# R210X.net
KiCad netlist of a schematic drawn in EAGLE
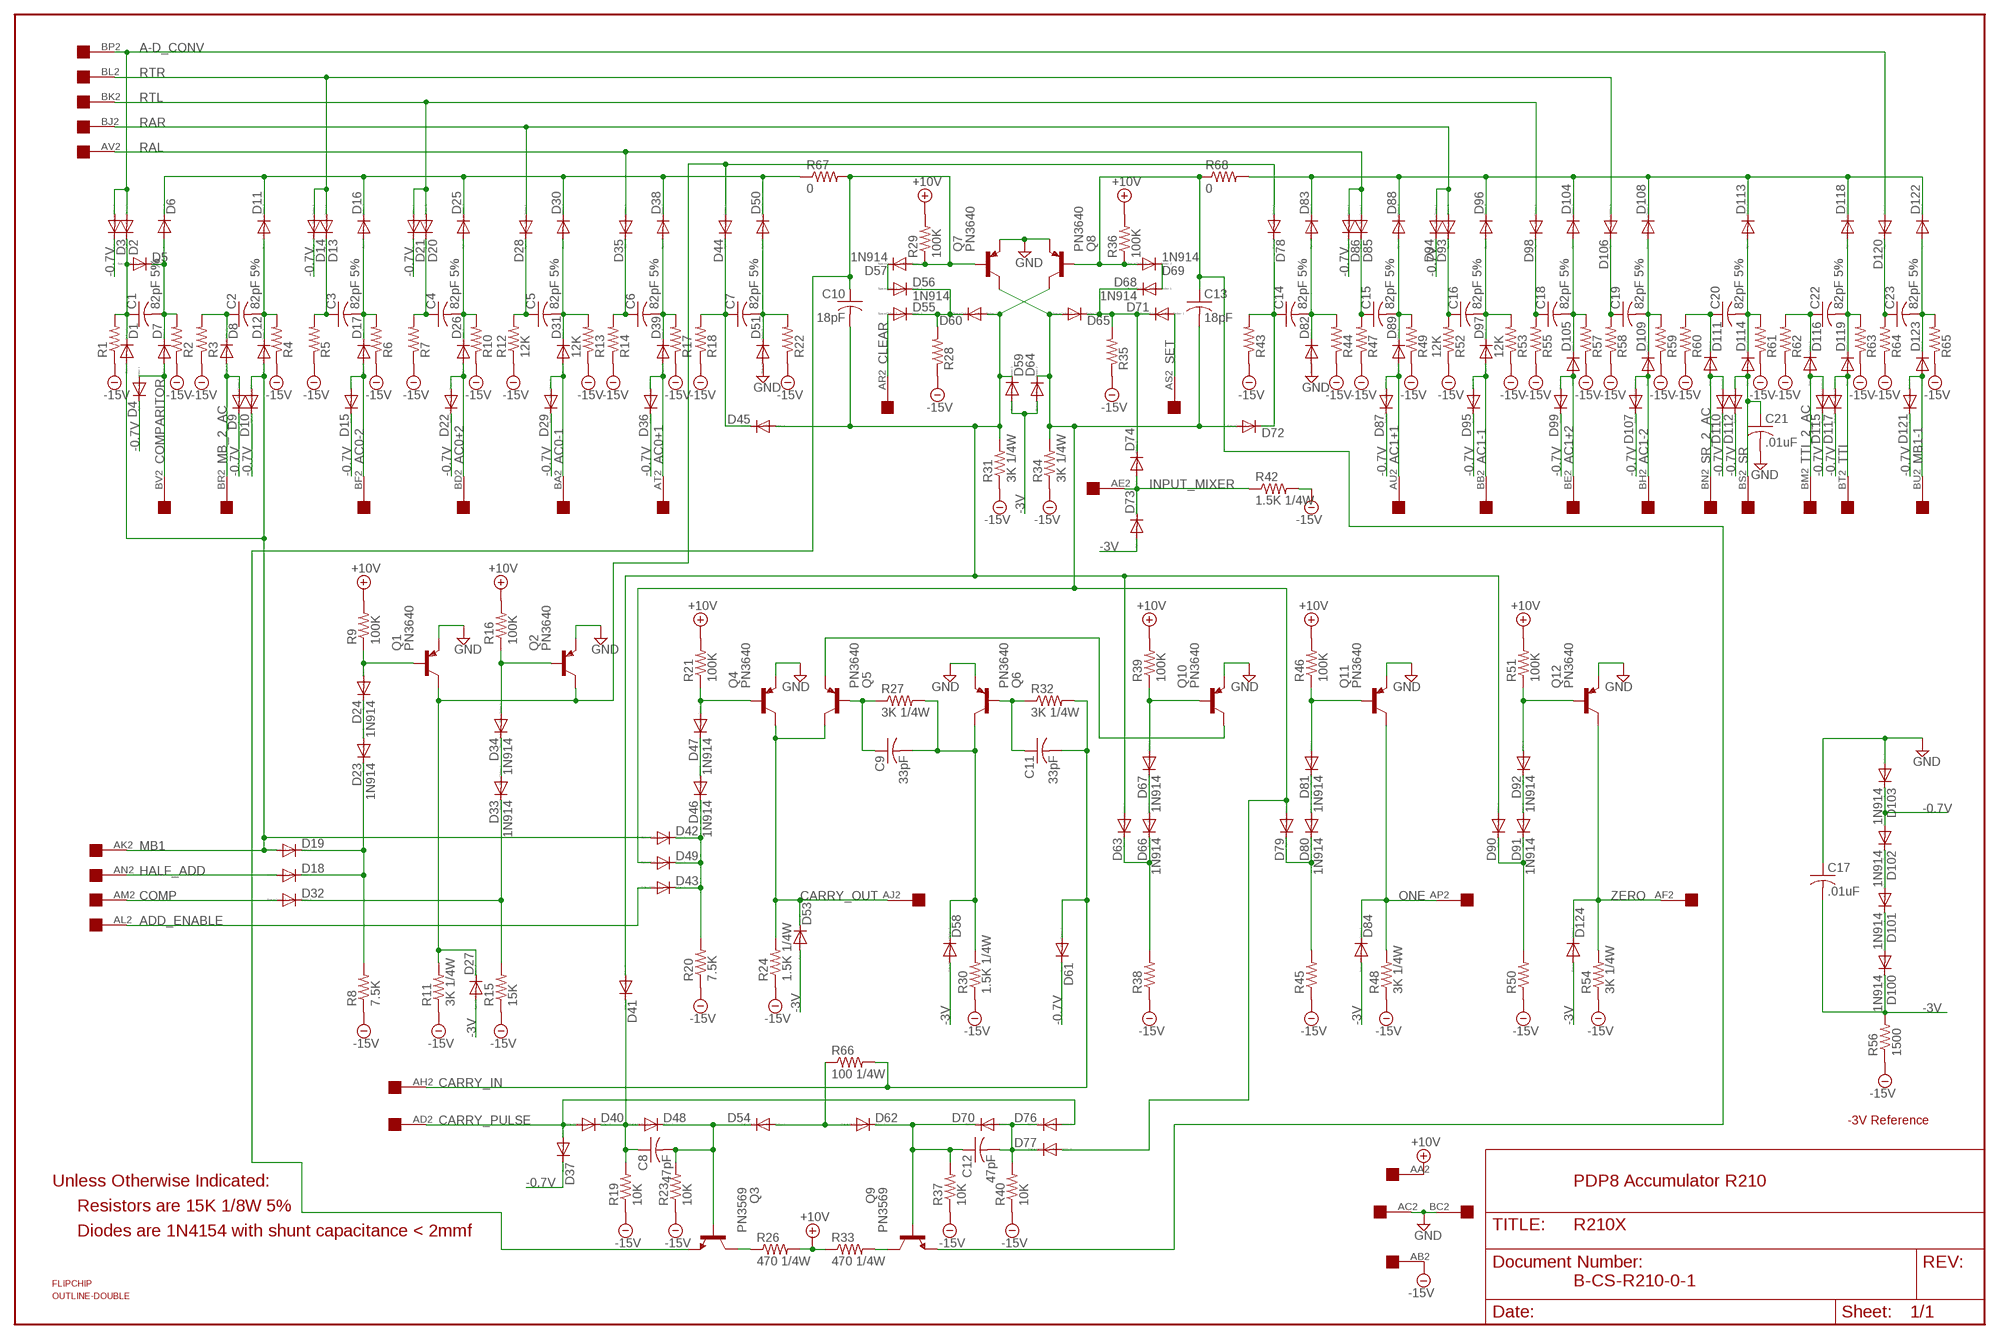
[diagram p0: schematic, sheet 1]

(export (version "E")
  (design (tool "Eeschema 10.0.6"))
  (components
    (comp (ref "C1")
      (value "82pF 5%")
      (footprint "eagle-import:C075-032X103")
      (libsource (lib "eagle-import") (part "C-US075-032X103"))
    )
    (comp (ref "C2")
      (value "82pF 5%")
      (footprint "eagle-import:C075-032X103")
      (libsource (lib "eagle-import") (part "C-US075-032X103"))
    )
    (comp (ref "C3")
      (value "82pF 5%")
      (footprint "eagle-import:C075-032X103")
      (libsource (lib "eagle-import") (part "C-US075-032X103"))
    )
    (comp (ref "C4")
      (value "82pF 5%")
      (footprint "eagle-import:C075-032X103")
      (libsource (lib "eagle-import") (part "C-US075-032X103"))
    )
    (comp (ref "C5")
      (value "82pF 5%")
      (footprint "eagle-import:C075-032X103")
      (libsource (lib "eagle-import") (part "C-US075-032X103"))
    )
    (comp (ref "C6")
      (value "82pF 5%")
      (footprint "eagle-import:C075-032X103")
      (libsource (lib "eagle-import") (part "C-US075-032X103"))
    )
    (comp (ref "C7")
      (value "82pF 5%")
      (footprint "eagle-import:C075-032X103")
      (libsource (lib "eagle-import") (part "C-US075-032X103"))
    )
    (comp (ref "C8")
      (value "47pF")
      (footprint "eagle-import:C075-032X103")
      (libsource (lib "eagle-import") (part "C-US075-032X103"))
    )
    (comp (ref "C9")
      (value "33pF")
      (footprint "eagle-import:C075-032X103")
      (libsource (lib "eagle-import") (part "C-US075-032X103"))
    )
    (comp (ref "C10")
      (value "18pF")
      (footprint "eagle-import:C075-032X103")
      (libsource (lib "eagle-import") (part "C-US075-032X103"))
    )
    (comp (ref "C11")
      (value "33pF")
      (footprint "eagle-import:C075-032X103")
      (libsource (lib "eagle-import") (part "C-US075-032X103"))
    )
    (comp (ref "C12")
      (value "47pF")
      (footprint "eagle-import:C075-032X103")
      (libsource (lib "eagle-import") (part "C-US075-032X103"))
    )
    (comp (ref "C13")
      (value "18pF")
      (footprint "eagle-import:C075-032X103")
      (libsource (lib "eagle-import") (part "C-US075-032X103"))
    )
    (comp (ref "C14")
      (value "82pF 5%")
      (footprint "eagle-import:C075-032X103")
      (libsource (lib "eagle-import") (part "C-US075-032X103"))
    )
    (comp (ref "C15")
      (value "82pF 5%")
      (footprint "eagle-import:C075-032X103")
      (libsource (lib "eagle-import") (part "C-US075-032X103"))
    )
    (comp (ref "C16")
      (value "82pF 5%")
      (footprint "eagle-import:C075-032X103")
      (libsource (lib "eagle-import") (part "C-US075-032X103"))
    )
    (comp (ref "C17")
      (value ".01uF")
      (footprint "eagle-import:C050-025X075")
      (libsource (lib "eagle-import") (part "C-US050-025X075"))
    )
    (comp (ref "C18")
      (value "82pF 5%")
      (footprint "eagle-import:C075-032X103")
      (libsource (lib "eagle-import") (part "C-US075-032X103"))
    )
    (comp (ref "C19")
      (value "82pF 5%")
      (footprint "eagle-import:C075-032X103")
      (libsource (lib "eagle-import") (part "C-US075-032X103"))
    )
    (comp (ref "C20")
      (value "82pF 5%")
      (footprint "eagle-import:C075-032X103")
      (libsource (lib "eagle-import") (part "C-US075-032X103"))
    )
    (comp (ref "C21")
      (value ".01uF")
      (footprint "eagle-import:C050-025X075")
      (libsource (lib "eagle-import") (part "C-US050-025X075"))
    )
    (comp (ref "C22")
      (value "82pF 5%")
      (footprint "eagle-import:C075-032X103")
      (libsource (lib "eagle-import") (part "C-US075-032X103"))
    )
    (comp (ref "C23")
      (value "82pF 5%")
      (footprint "eagle-import:C075-032X103")
      (libsource (lib "eagle-import") (part "C-US075-032X103"))
    )
    (comp (ref "D1")
      (value "1N4148DO35-10")
      (footprint "eagle-import:DO35-10")
      (libsource (lib "eagle-import") (part "1N4148DO35-10"))
    )
    (comp (ref "D2")
      (value "1N4148DO35-10")
      (footprint "eagle-import:DO35-10")
      (libsource (lib "eagle-import") (part "1N4148DO35-10"))
    )
    (comp (ref "D3")
      (value "1N4148DO35-10")
      (footprint "eagle-import:DO35-10")
      (libsource (lib "eagle-import") (part "1N4148DO35-10"))
    )
    (comp (ref "D4")
      (value "1N4148DO35-10")
      (footprint "eagle-import:DO35-10")
      (libsource (lib "eagle-import") (part "1N4148DO35-10"))
    )
    (comp (ref "D5")
      (value "1N4148DO35-10")
      (footprint "eagle-import:DO35-10")
      (libsource (lib "eagle-import") (part "1N4148DO35-10"))
    )
    (comp (ref "D6")
      (value "1N4148DO35-10")
      (footprint "eagle-import:DO35-10")
      (libsource (lib "eagle-import") (part "1N4148DO35-10"))
    )
    (comp (ref "D7")
      (value "1N4148DO35-10")
      (footprint "eagle-import:DO35-10")
      (libsource (lib "eagle-import") (part "1N4148DO35-10"))
    )
    (comp (ref "D8")
      (value "1N4148DO35-10")
      (footprint "eagle-import:DO35-10")
      (libsource (lib "eagle-import") (part "1N4148DO35-10"))
    )
    (comp (ref "D9")
      (value "1N4148DO35-10")
      (footprint "eagle-import:DO35-10")
      (libsource (lib "eagle-import") (part "1N4148DO35-10"))
    )
    (comp (ref "D10")
      (value "1N4148DO35-10")
      (footprint "eagle-import:DO35-10")
      (libsource (lib "eagle-import") (part "1N4148DO35-10"))
    )
    (comp (ref "D11")
      (value "1N4148DO35-10")
      (footprint "eagle-import:DO35-10")
      (libsource (lib "eagle-import") (part "1N4148DO35-10"))
    )
    (comp (ref "D12")
      (value "1N4148DO35-10")
      (footprint "eagle-import:DO35-10")
      (libsource (lib "eagle-import") (part "1N4148DO35-10"))
    )
    (comp (ref "D13")
      (value "1N4148DO35-10")
      (footprint "eagle-import:DO35-10")
      (libsource (lib "eagle-import") (part "1N4148DO35-10"))
    )
    (comp (ref "D14")
      (value "1N4148DO35-10")
      (footprint "eagle-import:DO35-10")
      (libsource (lib "eagle-import") (part "1N4148DO35-10"))
    )
    (comp (ref "D15")
      (value "1N4148DO35-10")
      (footprint "eagle-import:DO35-10")
      (libsource (lib "eagle-import") (part "1N4148DO35-10"))
    )
    (comp (ref "D16")
      (value "1N4148DO35-10")
      (footprint "eagle-import:DO35-10")
      (libsource (lib "eagle-import") (part "1N4148DO35-10"))
    )
    (comp (ref "D17")
      (value "1N4148DO35-10")
      (footprint "eagle-import:DO35-10")
      (libsource (lib "eagle-import") (part "1N4148DO35-10"))
    )
    (comp (ref "D18")
      (value "1N4148DO35-10")
      (footprint "eagle-import:DO35-10")
      (libsource (lib "eagle-import") (part "1N4148DO35-10"))
    )
    (comp (ref "D19")
      (value "1N4148DO35-10")
      (footprint "eagle-import:DO35-10")
      (libsource (lib "eagle-import") (part "1N4148DO35-10"))
    )
    (comp (ref "D20")
      (value "1N4148DO35-10")
      (footprint "eagle-import:DO35-10")
      (libsource (lib "eagle-import") (part "1N4148DO35-10"))
    )
    (comp (ref "D21")
      (value "1N4148DO35-10")
      (footprint "eagle-import:DO35-10")
      (libsource (lib "eagle-import") (part "1N4148DO35-10"))
    )
    (comp (ref "D22")
      (value "1N4148DO35-10")
      (footprint "eagle-import:DO35-10")
      (libsource (lib "eagle-import") (part "1N4148DO35-10"))
    )
    (comp (ref "D23")
      (value "1N914")
      (footprint "eagle-import:DO35-10")
      (libsource (lib "eagle-import") (part "1N4148DO35-10"))
    )
    (comp (ref "D24")
      (value "1N914")
      (footprint "eagle-import:DO35-10")
      (libsource (lib "eagle-import") (part "1N4148DO35-10"))
    )
    (comp (ref "D25")
      (value "1N4148DO35-10")
      (footprint "eagle-import:DO35-10")
      (libsource (lib "eagle-import") (part "1N4148DO35-10"))
    )
    (comp (ref "D26")
      (value "1N4148DO35-10")
      (footprint "eagle-import:DO35-10")
      (libsource (lib "eagle-import") (part "1N4148DO35-10"))
    )
    (comp (ref "D27")
      (value "1N4148DO35-10")
      (footprint "eagle-import:DO35-10")
      (libsource (lib "eagle-import") (part "1N4148DO35-10"))
    )
    (comp (ref "D28")
      (value "1N4148DO35-10")
      (footprint "eagle-import:DO35-10")
      (libsource (lib "eagle-import") (part "1N4148DO35-10"))
    )
    (comp (ref "D29")
      (value "1N4148DO35-10")
      (footprint "eagle-import:DO35-10")
      (libsource (lib "eagle-import") (part "1N4148DO35-10"))
    )
    (comp (ref "D30")
      (value "1N4148DO35-10")
      (footprint "eagle-import:DO35-10")
      (libsource (lib "eagle-import") (part "1N4148DO35-10"))
    )
    (comp (ref "D31")
      (value "1N4148DO35-10")
      (footprint "eagle-import:DO35-10")
      (libsource (lib "eagle-import") (part "1N4148DO35-10"))
    )
    (comp (ref "D32")
      (value "1N4148DO35-10")
      (footprint "eagle-import:DO35-10")
      (libsource (lib "eagle-import") (part "1N4148DO35-10"))
    )
    (comp (ref "D33")
      (value "1N914")
      (footprint "eagle-import:DO35-10")
      (libsource (lib "eagle-import") (part "1N4148DO35-10"))
    )
    (comp (ref "D34")
      (value "1N914")
      (footprint "eagle-import:DO35-10")
      (libsource (lib "eagle-import") (part "1N4148DO35-10"))
    )
    (comp (ref "D35")
      (value "1N4148DO35-10")
      (footprint "eagle-import:DO35-10")
      (libsource (lib "eagle-import") (part "1N4148DO35-10"))
    )
    (comp (ref "D36")
      (value "1N4148DO35-10")
      (footprint "eagle-import:DO35-10")
      (libsource (lib "eagle-import") (part "1N4148DO35-10"))
    )
    (comp (ref "D37")
      (value "1N4148DO35-10")
      (footprint "eagle-import:DO35-10")
      (libsource (lib "eagle-import") (part "1N4148DO35-10"))
    )
    (comp (ref "D38")
      (value "1N4148DO35-10")
      (footprint "eagle-import:DO35-10")
      (libsource (lib "eagle-import") (part "1N4148DO35-10"))
    )
    (comp (ref "D39")
      (value "1N4148DO35-10")
      (footprint "eagle-import:DO35-10")
      (libsource (lib "eagle-import") (part "1N4148DO35-10"))
    )
    (comp (ref "D40")
      (value "1N4148DO35-10")
      (footprint "eagle-import:DO35-10")
      (libsource (lib "eagle-import") (part "1N4148DO35-10"))
    )
    (comp (ref "D41")
      (value "1N4148DO35-10")
      (footprint "eagle-import:DO35-10")
      (libsource (lib "eagle-import") (part "1N4148DO35-10"))
    )
    (comp (ref "D42")
      (value "1N4148DO35-10")
      (footprint "eagle-import:DO35-10")
      (libsource (lib "eagle-import") (part "1N4148DO35-10"))
    )
    (comp (ref "D43")
      (value "1N4148DO35-10")
      (footprint "eagle-import:DO35-10")
      (libsource (lib "eagle-import") (part "1N4148DO35-10"))
    )
    (comp (ref "D44")
      (value "1N4148DO35-10")
      (footprint "eagle-import:DO35-10")
      (libsource (lib "eagle-import") (part "1N4148DO35-10"))
    )
    (comp (ref "D45")
      (value "1N4148DO35-10")
      (footprint "eagle-import:DO35-10")
      (libsource (lib "eagle-import") (part "1N4148DO35-10"))
    )
    (comp (ref "D46")
      (value "1N914")
      (footprint "eagle-import:DO35-10")
      (libsource (lib "eagle-import") (part "1N4148DO35-10"))
    )
    (comp (ref "D47")
      (value "1N914")
      (footprint "eagle-import:DO35-10")
      (libsource (lib "eagle-import") (part "1N4148DO35-10"))
    )
    (comp (ref "D48")
      (value "1N4148DO35-10")
      (footprint "eagle-import:DO35-10")
      (libsource (lib "eagle-import") (part "1N4148DO35-10"))
    )
    (comp (ref "D49")
      (value "1N4148DO35-10")
      (footprint "eagle-import:DO35-10")
      (libsource (lib "eagle-import") (part "1N4148DO35-10"))
    )
    (comp (ref "D50")
      (value "1N4148DO35-10")
      (footprint "eagle-import:DO35-10")
      (libsource (lib "eagle-import") (part "1N4148DO35-10"))
    )
    (comp (ref "D51")
      (value "1N4148DO35-10")
      (footprint "eagle-import:DO35-10")
      (libsource (lib "eagle-import") (part "1N4148DO35-10"))
    )
    (comp (ref "D53")
      (value "1N4148DO35-10")
      (footprint "eagle-import:DO35-10")
      (libsource (lib "eagle-import") (part "1N4148DO35-10"))
    )
    (comp (ref "D54")
      (value "1N4148DO35-10")
      (footprint "eagle-import:DO35-10")
      (libsource (lib "eagle-import") (part "1N4148DO35-10"))
    )
    (comp (ref "D55")
      (value "1N4148DO35-10")
      (footprint "eagle-import:DO35-10")
      (libsource (lib "eagle-import") (part "1N4148DO35-10"))
    )
    (comp (ref "D56")
      (value "1N914")
      (footprint "eagle-import:DO35-10")
      (libsource (lib "eagle-import") (part "1N4148DO35-10"))
    )
    (comp (ref "D57")
      (value "1N914")
      (footprint "eagle-import:DO35-10")
      (libsource (lib "eagle-import") (part "1N4148DO35-10"))
    )
    (comp (ref "D58")
      (value "1N4148DO35-10")
      (footprint "eagle-import:DO35-10")
      (libsource (lib "eagle-import") (part "1N4148DO35-10"))
    )
    (comp (ref "D59")
      (value "1N4148DO35-10")
      (footprint "eagle-import:DO35-10")
      (libsource (lib "eagle-import") (part "1N4148DO35-10"))
    )
    (comp (ref "D60")
      (value "1N4148DO35-10")
      (footprint "eagle-import:DO35-10")
      (libsource (lib "eagle-import") (part "1N4148DO35-10"))
    )
    (comp (ref "D61")
      (value "1N4148DO35-10")
      (footprint "eagle-import:DO35-10")
      (libsource (lib "eagle-import") (part "1N4148DO35-10"))
    )
    (comp (ref "D62")
      (value "1N4148DO35-10")
      (footprint "eagle-import:DO35-10")
      (libsource (lib "eagle-import") (part "1N4148DO35-10"))
    )
    (comp (ref "D63")
      (value "1N4148DO35-10")
      (footprint "eagle-import:DO35-10")
      (libsource (lib "eagle-import") (part "1N4148DO35-10"))
    )
    (comp (ref "D64")
      (value "1N4148DO35-10")
      (footprint "eagle-import:DO35-10")
      (libsource (lib "eagle-import") (part "1N4148DO35-10"))
    )
    (comp (ref "D65")
      (value "1N4148DO35-10")
      (footprint "eagle-import:DO35-10")
      (libsource (lib "eagle-import") (part "1N4148DO35-10"))
    )
    (comp (ref "D66")
      (value "1N914")
      (footprint "eagle-import:DO35-10")
      (libsource (lib "eagle-import") (part "1N4148DO35-10"))
    )
    (comp (ref "D67")
      (value "1N914")
      (footprint "eagle-import:DO35-10")
      (libsource (lib "eagle-import") (part "1N4148DO35-10"))
    )
    (comp (ref "D68")
      (value "1N914")
      (footprint "eagle-import:DO35-10")
      (libsource (lib "eagle-import") (part "1N4148DO35-10"))
    )
    (comp (ref "D69")
      (value "1N914")
      (footprint "eagle-import:DO35-10")
      (libsource (lib "eagle-import") (part "1N4148DO35-10"))
    )
    (comp (ref "D70")
      (value "1N4148DO35-10")
      (footprint "eagle-import:DO35-10")
      (libsource (lib "eagle-import") (part "1N4148DO35-10"))
    )
    (comp (ref "D71")
      (value "1N4148DO35-10")
      (footprint "eagle-import:DO35-10")
      (libsource (lib "eagle-import") (part "1N4148DO35-10"))
    )
    (comp (ref "D72")
      (value "1N4148DO35-10")
      (footprint "eagle-import:DO35-10")
      (libsource (lib "eagle-import") (part "1N4148DO35-10"))
    )
    (comp (ref "D73")
      (value "1N4148DO35-10")
      (footprint "eagle-import:DO35-10")
      (libsource (lib "eagle-import") (part "1N4148DO35-10"))
    )
    (comp (ref "D74")
      (value "1N4148DO35-10")
      (footprint "eagle-import:DO35-10")
      (libsource (lib "eagle-import") (part "1N4148DO35-10"))
    )
    (comp (ref "D76")
      (value "1N4148DO35-10")
      (footprint "eagle-import:DO35-10")
      (libsource (lib "eagle-import") (part "1N4148DO35-10"))
    )
    (comp (ref "D77")
      (value "1N4148DO35-10")
      (footprint "eagle-import:DO35-10")
      (libsource (lib "eagle-import") (part "1N4148DO35-10"))
    )
    (comp (ref "D78")
      (value "1N4148DO35-10")
      (footprint "eagle-import:DO35-10")
      (libsource (lib "eagle-import") (part "1N4148DO35-10"))
    )
    (comp (ref "D79")
      (value "1N4148DO35-10")
      (footprint "eagle-import:DO35-10")
      (libsource (lib "eagle-import") (part "1N4148DO35-10"))
    )
    (comp (ref "D80")
      (value "1N914")
      (footprint "eagle-import:DO35-10")
      (libsource (lib "eagle-import") (part "1N4148DO35-10"))
    )
    (comp (ref "D81")
      (value "1N914")
      (footprint "eagle-import:DO35-10")
      (libsource (lib "eagle-import") (part "1N4148DO35-10"))
    )
    (comp (ref "D82")
      (value "1N4148DO35-10")
      (footprint "eagle-import:DO35-10")
      (libsource (lib "eagle-import") (part "1N4148DO35-10"))
    )
    (comp (ref "D83")
      (value "1N4148DO35-10")
      (footprint "eagle-import:DO35-10")
      (libsource (lib "eagle-import") (part "1N4148DO35-10"))
    )
    (comp (ref "D84")
      (value "1N4148DO35-10")
      (footprint "eagle-import:DO35-10")
      (libsource (lib "eagle-import") (part "1N4148DO35-10"))
    )
    (comp (ref "D85")
      (value "1N4148DO35-10")
      (footprint "eagle-import:DO35-10")
      (libsource (lib "eagle-import") (part "1N4148DO35-10"))
    )
    (comp (ref "D86")
      (value "1N4148DO35-10")
      (footprint "eagle-import:DO35-10")
      (libsource (lib "eagle-import") (part "1N4148DO35-10"))
    )
    (comp (ref "D87")
      (value "1N4148DO35-10")
      (footprint "eagle-import:DO35-10")
      (libsource (lib "eagle-import") (part "1N4148DO35-10"))
    )
    (comp (ref "D88")
      (value "1N4148DO35-10")
      (footprint "eagle-import:DO35-10")
      (libsource (lib "eagle-import") (part "1N4148DO35-10"))
    )
    (comp (ref "D89")
      (value "1N4148DO35-10")
      (footprint "eagle-import:DO35-10")
      (libsource (lib "eagle-import") (part "1N4148DO35-10"))
    )
    (comp (ref "D90")
      (value "1N4148DO35-10")
      (footprint "eagle-import:DO35-10")
      (libsource (lib "eagle-import") (part "1N4148DO35-10"))
    )
    (comp (ref "D91")
      (value "1N914")
      (footprint "eagle-import:DO35-10")
      (libsource (lib "eagle-import") (part "1N4148DO35-10"))
    )
    (comp (ref "D92")
      (value "1N914")
      (footprint "eagle-import:DO35-10")
      (libsource (lib "eagle-import") (part "1N4148DO35-10"))
    )
    (comp (ref "D93")
      (value "1N4148DO35-10")
      (footprint "eagle-import:DO35-10")
      (libsource (lib "eagle-import") (part "1N4148DO35-10"))
    )
    (comp (ref "D94")
      (value "1N4148DO35-10")
      (footprint "eagle-import:DO35-10")
      (libsource (lib "eagle-import") (part "1N4148DO35-10"))
    )
    (comp (ref "D95")
      (value "1N4148DO35-10")
      (footprint "eagle-import:DO35-10")
      (libsource (lib "eagle-import") (part "1N4148DO35-10"))
    )
    (comp (ref "D96")
      (value "1N4148DO35-10")
      (footprint "eagle-import:DO35-10")
      (libsource (lib "eagle-import") (part "1N4148DO35-10"))
    )
    (comp (ref "D97")
      (value "1N4148DO35-10")
      (footprint "eagle-import:DO35-10")
      (libsource (lib "eagle-import") (part "1N4148DO35-10"))
    )
    (comp (ref "D98")
      (value "1N4148DO35-10")
      (footprint "eagle-import:DO35-10")
      (libsource (lib "eagle-import") (part "1N4148DO35-10"))
    )
    (comp (ref "D99")
      (value "1N4148DO35-10")
      (footprint "eagle-import:DO35-10")
      (libsource (lib "eagle-import") (part "1N4148DO35-10"))
    )
    (comp (ref "D100")
      (value "1N914")
      (footprint "eagle-import:DO35-10")
      (libsource (lib "eagle-import") (part "1N4148DO35-10"))
    )
    (comp (ref "D101")
      (value "1N914")
      (footprint "eagle-import:DO35-10")
      (libsource (lib "eagle-import") (part "1N4148DO35-10"))
    )
    (comp (ref "D102")
      (value "1N914")
      (footprint "eagle-import:DO35-10")
      (libsource (lib "eagle-import") (part "1N4148DO35-10"))
    )
    (comp (ref "D103")
      (value "1N914")
      (footprint "eagle-import:DO35-10")
      (libsource (lib "eagle-import") (part "1N4148DO35-10"))
    )
    (comp (ref "D104")
      (value "1N4148DO35-10")
      (footprint "eagle-import:DO35-10")
      (libsource (lib "eagle-import") (part "1N4148DO35-10"))
    )
    (comp (ref "D105")
      (value "1N4148DO35-10")
      (footprint "eagle-import:DO35-10")
      (libsource (lib "eagle-import") (part "1N4148DO35-10"))
    )
    (comp (ref "D106")
      (value "1N4148DO35-10")
      (footprint "eagle-import:DO35-10")
      (libsource (lib "eagle-import") (part "1N4148DO35-10"))
    )
    (comp (ref "D107")
      (value "1N4148DO35-10")
      (footprint "eagle-import:DO35-10")
      (libsource (lib "eagle-import") (part "1N4148DO35-10"))
    )
    (comp (ref "D108")
      (value "1N4148DO35-10")
      (footprint "eagle-import:DO35-10")
      (libsource (lib "eagle-import") (part "1N4148DO35-10"))
    )
    (comp (ref "D109")
      (value "1N4148DO35-10")
      (footprint "eagle-import:DO35-10")
      (libsource (lib "eagle-import") (part "1N4148DO35-10"))
    )
    (comp (ref "D110")
      (value "1N4148DO35-10")
      (footprint "eagle-import:DO35-10")
      (libsource (lib "eagle-import") (part "1N4148DO35-10"))
    )
    (comp (ref "D111")
      (value "1N4148DO35-10")
      (footprint "eagle-import:DO35-10")
      (libsource (lib "eagle-import") (part "1N4148DO35-10"))
    )
    (comp (ref "D112")
      (value "1N4148DO35-10")
      (footprint "eagle-import:DO35-10")
      (libsource (lib "eagle-import") (part "1N4148DO35-10"))
    )
    (comp (ref "D113")
      (value "1N4148DO35-10")
      (footprint "eagle-import:DO35-10")
      (libsource (lib "eagle-import") (part "1N4148DO35-10"))
    )
    (comp (ref "D114")
      (value "1N4148DO35-10")
      (footprint "eagle-import:DO35-10")
      (libsource (lib "eagle-import") (part "1N4148DO35-10"))
    )
    (comp (ref "D115")
      (value "1N4148DO35-10")
      (footprint "eagle-import:DO35-10")
      (libsource (lib "eagle-import") (part "1N4148DO35-10"))
    )
    (comp (ref "D116")
      (value "1N4148DO35-10")
      (footprint "eagle-import:DO35-10")
      (libsource (lib "eagle-import") (part "1N4148DO35-10"))
    )
    (comp (ref "D117")
      (value "1N4148DO35-10")
      (footprint "eagle-import:DO35-10")
      (libsource (lib "eagle-import") (part "1N4148DO35-10"))
    )
    (comp (ref "D118")
      (value "1N4148DO35-10")
      (footprint "eagle-import:DO35-10")
      (libsource (lib "eagle-import") (part "1N4148DO35-10"))
    )
    (comp (ref "D119")
      (value "1N4148DO35-10")
      (footprint "eagle-import:DO35-10")
      (libsource (lib "eagle-import") (part "1N4148DO35-10"))
    )
    (comp (ref "D120")
      (value "1N4148DO35-10")
      (footprint "eagle-import:DO35-10")
      (libsource (lib "eagle-import") (part "1N4148DO35-10"))
    )
    (comp (ref "D121")
      (value "1N4148DO35-10")
      (footprint "eagle-import:DO35-10")
      (libsource (lib "eagle-import") (part "1N4148DO35-10"))
    )
    (comp (ref "D122")
      (value "1N4148DO35-10")
      (footprint "eagle-import:DO35-10")
      (libsource (lib "eagle-import") (part "1N4148DO35-10"))
    )
    (comp (ref "D123")
      (value "1N4148DO35-10")
      (footprint "eagle-import:DO35-10")
      (libsource (lib "eagle-import") (part "1N4148DO35-10"))
    )
    (comp (ref "D124")
      (value "1N4148DO35-10")
      (footprint "eagle-import:DO35-10")
      (libsource (lib "eagle-import") (part "1N4148DO35-10"))
    )
    (comp (ref "Q1")
      (value "PN3640")
      (footprint "eagle-import:TO39")
      (libsource (lib "eagle-import") (part "2N3637"))
    )
    (comp (ref "Q2")
      (value "PN3640")
      (footprint "eagle-import:TO39")
      (libsource (lib "eagle-import") (part "2N3637"))
    )
    (comp (ref "Q3")
      (value "PN3569")
      (footprint "eagle-import:TO5")
      (libsource (lib "eagle-import") (part "2N2102"))
    )
    (comp (ref "Q4")
      (value "PN3640")
      (footprint "eagle-import:TO39")
      (libsource (lib "eagle-import") (part "2N3637"))
    )
    (comp (ref "Q5")
      (value "PN3640")
      (footprint "eagle-import:TO39")
      (libsource (lib "eagle-import") (part "2N3637"))
    )
    (comp (ref "Q6")
      (value "PN3640")
      (footprint "eagle-import:TO39")
      (libsource (lib "eagle-import") (part "2N3637"))
    )
    (comp (ref "Q7")
      (value "PN3640")
      (footprint "eagle-import:TO39")
      (libsource (lib "eagle-import") (part "2N3637"))
    )
    (comp (ref "Q8")
      (value "PN3640")
      (footprint "eagle-import:TO39")
      (libsource (lib "eagle-import") (part "2N3637"))
    )
    (comp (ref "Q9")
      (value "PN3569")
      (footprint "eagle-import:TO5")
      (libsource (lib "eagle-import") (part "2N2102"))
    )
    (comp (ref "Q10")
      (value "PN3640")
      (footprint "eagle-import:TO39")
      (libsource (lib "eagle-import") (part "2N3637"))
    )
    (comp (ref "Q11")
      (value "PN3640")
      (footprint "eagle-import:TO39")
      (libsource (lib "eagle-import") (part "2N3637"))
    )
    (comp (ref "Q12")
      (value "PN3640")
      (footprint "eagle-import:TO39")
      (libsource (lib "eagle-import") (part "2N3637"))
    )
    (comp (ref "R1")
      (value "R-US_0207/10")
      (footprint "eagle-import:0207_10")
      (libsource (lib "eagle-import") (part "R-US_0207/10"))
    )
    (comp (ref "R2")
      (value "R-US_0207/10")
      (footprint "eagle-import:0207_10")
      (libsource (lib "eagle-import") (part "R-US_0207/10"))
    )
    (comp (ref "R3")
      (value "R-US_0207/10")
      (footprint "eagle-import:0207_10")
      (libsource (lib "eagle-import") (part "R-US_0207/10"))
    )
    (comp (ref "R4")
      (value "R-US_0207/10")
      (footprint "eagle-import:0207_10")
      (libsource (lib "eagle-import") (part "R-US_0207/10"))
    )
    (comp (ref "R5")
      (value "R-US_0207/10")
      (footprint "eagle-import:0207_10")
      (libsource (lib "eagle-import") (part "R-US_0207/10"))
    )
    (comp (ref "R6")
      (value "R-US_0207/10")
      (footprint "eagle-import:0207_10")
      (libsource (lib "eagle-import") (part "R-US_0207/10"))
    )
    (comp (ref "R7")
      (value "R-US_0207/10")
      (footprint "eagle-import:0207_10")
      (libsource (lib "eagle-import") (part "R-US_0207/10"))
    )
    (comp (ref "R8")
      (value "7.5K")
      (footprint "eagle-import:0207_10")
      (libsource (lib "eagle-import") (part "R-US_0207/10"))
    )
    (comp (ref "R9")
      (value "100K")
      (footprint "eagle-import:0207_10")
      (libsource (lib "eagle-import") (part "R-US_0207/10"))
    )
    (comp (ref "R10")
      (value "R-US_0207/10")
      (footprint "eagle-import:0207_10")
      (libsource (lib "eagle-import") (part "R-US_0207/10"))
    )
    (comp (ref "R11")
      (value "3K 1/4W")
      (footprint "eagle-import:0207_10")
      (libsource (lib "eagle-import") (part "R-US_0207/10"))
    )
    (comp (ref "R12")
      (value "12K")
      (footprint "eagle-import:0207_10")
      (libsource (lib "eagle-import") (part "R-US_0207/10"))
    )
    (comp (ref "R13")
      (value "12K")
      (footprint "eagle-import:0207_10")
      (libsource (lib "eagle-import") (part "R-US_0207/10"))
    )
    (comp (ref "R14")
      (value "R-US_0207/10")
      (footprint "eagle-import:0207_10")
      (libsource (lib "eagle-import") (part "R-US_0207/10"))
    )
    (comp (ref "R15")
      (value "15K")
      (footprint "eagle-import:0207_10")
      (libsource (lib "eagle-import") (part "R-US_0207/10"))
    )
    (comp (ref "R16")
      (value "100K")
      (footprint "eagle-import:0207_10")
      (libsource (lib "eagle-import") (part "R-US_0207/10"))
    )
    (comp (ref "R17")
      (value "R-US_0207/10")
      (footprint "eagle-import:0207_10")
      (libsource (lib "eagle-import") (part "R-US_0207/10"))
    )
    (comp (ref "R18")
      (value "R-US_0207/10")
      (footprint "eagle-import:0207_10")
      (libsource (lib "eagle-import") (part "R-US_0207/10"))
    )
    (comp (ref "R19")
      (value "10K")
      (footprint "eagle-import:0207_10")
      (libsource (lib "eagle-import") (part "R-US_0207/10"))
    )
    (comp (ref "R20")
      (value "7.5K")
      (footprint "eagle-import:0207_10")
      (libsource (lib "eagle-import") (part "R-US_0207/10"))
    )
    (comp (ref "R21")
      (value "100K")
      (footprint "eagle-import:0207_10")
      (libsource (lib "eagle-import") (part "R-US_0207/10"))
    )
    (comp (ref "R22")
      (value "R-US_0207/10")
      (footprint "eagle-import:0207_10")
      (libsource (lib "eagle-import") (part "R-US_0207/10"))
    )
    (comp (ref "R23")
      (value "10K")
      (footprint "eagle-import:0207_10")
      (libsource (lib "eagle-import") (part "R-US_0207/10"))
    )
    (comp (ref "R24")
      (value "1.5K 1/4W")
      (footprint "eagle-import:0207_10")
      (libsource (lib "eagle-import") (part "R-US_0207/10"))
    )
    (comp (ref "R26")
      (value "470 1/4W")
      (footprint "eagle-import:0207_10")
      (libsource (lib "eagle-import") (part "R-US_0207/10"))
    )
    (comp (ref "R27")
      (value "3K 1/4W")
      (footprint "eagle-import:0207_10")
      (libsource (lib "eagle-import") (part "R-US_0207/10"))
    )
    (comp (ref "R28")
      (value "R-US_0207/10")
      (footprint "eagle-import:0207_10")
      (libsource (lib "eagle-import") (part "R-US_0207/10"))
    )
    (comp (ref "R29")
      (value "100K")
      (footprint "eagle-import:0207_10")
      (libsource (lib "eagle-import") (part "R-US_0207/10"))
    )
    (comp (ref "R30")
      (value "1.5K 1/4W")
      (footprint "eagle-import:0207_10")
      (libsource (lib "eagle-import") (part "R-US_0207/10"))
    )
    (comp (ref "R31")
      (value "3K 1/4W")
      (footprint "eagle-import:0207_10")
      (libsource (lib "eagle-import") (part "R-US_0207/10"))
    )
    (comp (ref "R32")
      (value "3K 1/4W")
      (footprint "eagle-import:0207_10")
      (libsource (lib "eagle-import") (part "R-US_0207/10"))
    )
    (comp (ref "R33")
      (value "470 1/4W")
      (footprint "eagle-import:0207_10")
      (libsource (lib "eagle-import") (part "R-US_0207/10"))
    )
    (comp (ref "R34")
      (value "3K 1/4W")
      (footprint "eagle-import:0207_10")
      (libsource (lib "eagle-import") (part "R-US_0207/10"))
    )
    (comp (ref "R35")
      (value "R-US_0207/10")
      (footprint "eagle-import:0207_10")
      (libsource (lib "eagle-import") (part "R-US_0207/10"))
    )
    (comp (ref "R36")
      (value "100K")
      (footprint "eagle-import:0207_10")
      (libsource (lib "eagle-import") (part "R-US_0207/10"))
    )
    (comp (ref "R37")
      (value "10K")
      (footprint "eagle-import:0207_10")
      (libsource (lib "eagle-import") (part "R-US_0207/10"))
    )
    (comp (ref "R38")
      (value "R-US_0207/10")
      (footprint "eagle-import:0207_10")
      (libsource (lib "eagle-import") (part "R-US_0207/10"))
    )
    (comp (ref "R39")
      (value "100K")
      (footprint "eagle-import:0207_10")
      (libsource (lib "eagle-import") (part "R-US_0207/10"))
    )
    (comp (ref "R40")
      (value "10K")
      (footprint "eagle-import:0207_10")
      (libsource (lib "eagle-import") (part "R-US_0207/10"))
    )
    (comp (ref "R42")
      (value "1.5K 1/4W")
      (footprint "eagle-import:0207_10")
      (libsource (lib "eagle-import") (part "R-US_0207/10"))
    )
    (comp (ref "R43")
      (value "R-US_0207/10")
      (footprint "eagle-import:0207_10")
      (libsource (lib "eagle-import") (part "R-US_0207/10"))
    )
    (comp (ref "R44")
      (value "R-US_0207/10")
      (footprint "eagle-import:0207_10")
      (libsource (lib "eagle-import") (part "R-US_0207/10"))
    )
    (comp (ref "R45")
      (value "R-US_0207/10")
      (footprint "eagle-import:0207_10")
      (libsource (lib "eagle-import") (part "R-US_0207/10"))
    )
    (comp (ref "R46")
      (value "100K")
      (footprint "eagle-import:0207_10")
      (libsource (lib "eagle-import") (part "R-US_0207/10"))
    )
    (comp (ref "R47")
      (value "R-US_0207/10")
      (footprint "eagle-import:0207_10")
      (libsource (lib "eagle-import") (part "R-US_0207/10"))
    )
    (comp (ref "R48")
      (value "3K 1/4W")
      (footprint "eagle-import:0207_10")
      (libsource (lib "eagle-import") (part "R-US_0207/10"))
    )
    (comp (ref "R49")
      (value "R-US_0207/10")
      (footprint "eagle-import:0207_10")
      (libsource (lib "eagle-import") (part "R-US_0207/10"))
    )
    (comp (ref "R50")
      (value "R-US_0207/10")
      (footprint "eagle-import:0207_10")
      (libsource (lib "eagle-import") (part "R-US_0207/10"))
    )
    (comp (ref "R51")
      (value "100K")
      (footprint "eagle-import:0207_10")
      (libsource (lib "eagle-import") (part "R-US_0207/10"))
    )
    (comp (ref "R52")
      (value "12K")
      (footprint "eagle-import:0207_10")
      (libsource (lib "eagle-import") (part "R-US_0207/10"))
    )
    (comp (ref "R53")
      (value "12K")
      (footprint "eagle-import:0207_10")
      (libsource (lib "eagle-import") (part "R-US_0207/10"))
    )
    (comp (ref "R54")
      (value "3K 1/4W")
      (footprint "eagle-import:0207_10")
      (libsource (lib "eagle-import") (part "R-US_0207/10"))
    )
    (comp (ref "R55")
      (value "R-US_0207/10")
      (footprint "eagle-import:0207_10")
      (libsource (lib "eagle-import") (part "R-US_0207/10"))
    )
    (comp (ref "R56")
      (value "1500")
      (footprint "eagle-import:0207_10")
      (libsource (lib "eagle-import") (part "R-US_0207/10"))
    )
    (comp (ref "R57")
      (value "R-US_0207/10")
      (footprint "eagle-import:0207_10")
      (libsource (lib "eagle-import") (part "R-US_0207/10"))
    )
    (comp (ref "R58")
      (value "R-US_0207/10")
      (footprint "eagle-import:0207_10")
      (libsource (lib "eagle-import") (part "R-US_0207/10"))
    )
    (comp (ref "R59")
      (value "R-US_0207/10")
      (footprint "eagle-import:0207_10")
      (libsource (lib "eagle-import") (part "R-US_0207/10"))
    )
    (comp (ref "R60")
      (value "R-US_0207/10")
      (footprint "eagle-import:0207_10")
      (libsource (lib "eagle-import") (part "R-US_0207/10"))
    )
    (comp (ref "R61")
      (value "R-US_0207/10")
      (footprint "eagle-import:0207_10")
      (libsource (lib "eagle-import") (part "R-US_0207/10"))
    )
    (comp (ref "R62")
      (value "R-US_0207/10")
      (footprint "eagle-import:0207_10")
      (libsource (lib "eagle-import") (part "R-US_0207/10"))
    )
    (comp (ref "R63")
      (value "R-US_0207/10")
      (footprint "eagle-import:0207_10")
      (libsource (lib "eagle-import") (part "R-US_0207/10"))
    )
    (comp (ref "R64")
      (value "R-US_0207/10")
      (footprint "eagle-import:0207_10")
      (libsource (lib "eagle-import") (part "R-US_0207/10"))
    )
    (comp (ref "R65")
      (value "R-US_0207/10")
      (footprint "eagle-import:0207_10")
      (libsource (lib "eagle-import") (part "R-US_0207/10"))
    )
    (comp (ref "R66")
      (value "100 1/4W")
      (footprint "eagle-import:0207_10")
      (libsource (lib "eagle-import") (part "R-US_0207/10"))
    )
    (comp (ref "R67")
      (value "0")
      (footprint "eagle-import:0207_10")
      (libsource (lib "eagle-import") (part "R-US_0207/10"))
    )
    (comp (ref "R68")
      (value "0")
      (footprint "eagle-import:0207_10")
      (libsource (lib "eagle-import") (part "R-US_0207/10"))
    )
    (comp (ref "U$1")
      (value "DOUBLE")
      (footprint "eagle-import:EDGE-CON4")
      (libsource (lib "eagle-import") (part "DOUBLE"))
    )
    (comp (ref "U$2")
      (value "FLIPCHIP")
      (footprint "eagle-import:FLIPCHIP")
      (libsource (lib "eagle-import") (part "FLIPCHIP"))
    )
    (comp (ref "U$3")
      (value "OUTLINE-DOUBLE")
      (footprint "eagle-import:DOUBLE")
      (libsource (lib "eagle-import") (part "OUTLINE-DOUBLE"))
    )
  )
  (nets
    (net (code "1") (name "+10V") (class "Default")
      (node (ref "R16") (pin "2") (pinfunction "2_2") (pintype "passive"))
      (node (ref "R21") (pin "2") (pinfunction "2_2") (pintype "passive"))
      (node (ref "R26") (pin "2") (pinfunction "2_2") (pintype "passive"))
      (node (ref "R29") (pin "2") (pinfunction "2_2") (pintype "passive"))
      (node (ref "R33") (pin "1") (pinfunction "1_1") (pintype "passive"))
      (node (ref "R36") (pin "2") (pinfunction "2_2") (pintype "passive"))
      (node (ref "R39") (pin "2") (pinfunction "2_2") (pintype "passive"))
      (node (ref "R46") (pin "2") (pinfunction "2_2") (pintype "passive"))
      (node (ref "R51") (pin "2") (pinfunction "2_2") (pintype "passive"))
      (node (ref "R9") (pin "2") (pinfunction "2_2") (pintype "passive"))
      (node (ref "U$1") (pin "AA2") (pinfunction "1_AA2") (pintype "bidirectional"))
    )
    (net (code "2") (name "-15V") (class "Default")
      (node (ref "R1") (pin "1") (pinfunction "1_1") (pintype "passive"))
      (node (ref "R10") (pin "1") (pinfunction "1_1") (pintype "passive"))
      (node (ref "R11") (pin "1") (pinfunction "1_1") (pintype "passive"))
      (node (ref "R12") (pin "1") (pinfunction "1_1") (pintype "passive"))
      (node (ref "R13") (pin "1") (pinfunction "1_1") (pintype "passive"))
      (node (ref "R14") (pin "1") (pinfunction "1_1") (pintype "passive"))
      (node (ref "R15") (pin "1") (pinfunction "1_1") (pintype "passive"))
      (node (ref "R17") (pin "1") (pinfunction "1_1") (pintype "passive"))
      (node (ref "R18") (pin "1") (pinfunction "1_1") (pintype "passive"))
      (node (ref "R19") (pin "1") (pinfunction "1_1") (pintype "passive"))
      (node (ref "R2") (pin "1") (pinfunction "1_1") (pintype "passive"))
      (node (ref "R20") (pin "1") (pinfunction "1_1") (pintype "passive"))
      (node (ref "R22") (pin "1") (pinfunction "1_1") (pintype "passive"))
      (node (ref "R23") (pin "1") (pinfunction "1_1") (pintype "passive"))
      (node (ref "R24") (pin "1") (pinfunction "1_1") (pintype "passive"))
      (node (ref "R28") (pin "1") (pinfunction "1_1") (pintype "passive"))
      (node (ref "R3") (pin "1") (pinfunction "1_1") (pintype "passive"))
      (node (ref "R30") (pin "1") (pinfunction "1_1") (pintype "passive"))
      (node (ref "R31") (pin "1") (pinfunction "1_1") (pintype "passive"))
      (node (ref "R34") (pin "1") (pinfunction "1_1") (pintype "passive"))
      (node (ref "R35") (pin "1") (pinfunction "1_1") (pintype "passive"))
      (node (ref "R37") (pin "1") (pinfunction "1_1") (pintype "passive"))
      (node (ref "R38") (pin "1") (pinfunction "1_1") (pintype "passive"))
      (node (ref "R4") (pin "1") (pinfunction "1_1") (pintype "passive"))
      (node (ref "R40") (pin "1") (pinfunction "1_1") (pintype "passive"))
      (node (ref "R42") (pin "2") (pinfunction "2_2") (pintype "passive"))
      (node (ref "R43") (pin "1") (pinfunction "1_1") (pintype "passive"))
      (node (ref "R44") (pin "1") (pinfunction "1_1") (pintype "passive"))
      (node (ref "R45") (pin "1") (pinfunction "1_1") (pintype "passive"))
      (node (ref "R47") (pin "1") (pinfunction "1_1") (pintype "passive"))
      (node (ref "R48") (pin "1") (pinfunction "1_1") (pintype "passive"))
      (node (ref "R49") (pin "1") (pinfunction "1_1") (pintype "passive"))
      (node (ref "R5") (pin "1") (pinfunction "1_1") (pintype "passive"))
      (node (ref "R50") (pin "1") (pinfunction "1_1") (pintype "passive"))
      (node (ref "R52") (pin "1") (pinfunction "1_1") (pintype "passive"))
      (node (ref "R53") (pin "1") (pinfunction "1_1") (pintype "passive"))
      (node (ref "R54") (pin "1") (pinfunction "1_1") (pintype "passive"))
      (node (ref "R55") (pin "1") (pinfunction "1_1") (pintype "passive"))
      (node (ref "R56") (pin "1") (pinfunction "1_1") (pintype "passive"))
      (node (ref "R57") (pin "1") (pinfunction "1_1") (pintype "passive"))
      (node (ref "R58") (pin "1") (pinfunction "1_1") (pintype "passive"))
      (node (ref "R59") (pin "1") (pinfunction "1_1") (pintype "passive"))
      (node (ref "R6") (pin "1") (pinfunction "1_1") (pintype "passive"))
      (node (ref "R60") (pin "1") (pinfunction "1_1") (pintype "passive"))
      (node (ref "R61") (pin "1") (pinfunction "1_1") (pintype "passive"))
      (node (ref "R62") (pin "1") (pinfunction "1_1") (pintype "passive"))
      (node (ref "R63") (pin "1") (pinfunction "1_1") (pintype "passive"))
      (node (ref "R64") (pin "1") (pinfunction "1_1") (pintype "passive"))
      (node (ref "R65") (pin "1") (pinfunction "1_1") (pintype "passive"))
      (node (ref "R7") (pin "1") (pinfunction "1_1") (pintype "passive"))
      (node (ref "R8") (pin "1") (pinfunction "1_1") (pintype "passive"))
      (node (ref "U$1") (pin "AB2") (pinfunction "1_AB2") (pintype "bidirectional"))
    )
    (net (code "3") (name "/-0.7V") (class "Default")
      (node (ref "D10") (pin "C") (pinfunction "C_C") (pintype "passive"))
      (node (ref "D102") (pin "A") (pinfunction "A_A") (pintype "passive"))
      (node (ref "D103") (pin "C") (pinfunction "C_C") (pintype "passive"))
      (node (ref "D107") (pin "C") (pinfunction "C_C") (pintype "passive"))
      (node (ref "D110") (pin "C") (pinfunction "C_C") (pintype "passive"))
      (node (ref "D112") (pin "C") (pinfunction "C_C") (pintype "passive"))
      (node (ref "D115") (pin "C") (pinfunction "C_C") (pintype "passive"))
      (node (ref "D117") (pin "C") (pinfunction "C_C") (pintype "passive"))
      (node (ref "D121") (pin "C") (pinfunction "C_C") (pintype "passive"))
      (node (ref "D14") (pin "C") (pinfunction "C_C") (pintype "passive"))
      (node (ref "D15") (pin "C") (pinfunction "C_C") (pintype "passive"))
      (node (ref "D21") (pin "C") (pinfunction "C_C") (pintype "passive"))
      (node (ref "D22") (pin "C") (pinfunction "C_C") (pintype "passive"))
      (node (ref "D29") (pin "C") (pinfunction "C_C") (pintype "passive"))
      (node (ref "D3") (pin "C") (pinfunction "C_C") (pintype "passive"))
      (node (ref "D36") (pin "C") (pinfunction "C_C") (pintype "passive"))
      (node (ref "D37") (pin "C") (pinfunction "C_C") (pintype "passive"))
      (node (ref "D4") (pin "C") (pinfunction "C_C") (pintype "passive"))
      (node (ref "D61") (pin "C") (pinfunction "C_C") (pintype "passive"))
      (node (ref "D86") (pin "C") (pinfunction "C_C") (pintype "passive"))
      (node (ref "D87") (pin "C") (pinfunction "C_C") (pintype "passive"))
      (node (ref "D9") (pin "C") (pinfunction "C_C") (pintype "passive"))
      (node (ref "D94") (pin "C") (pinfunction "C_C") (pintype "passive"))
      (node (ref "D95") (pin "C") (pinfunction "C_C") (pintype "passive"))
      (node (ref "D99") (pin "C") (pinfunction "C_C") (pintype "passive"))
    )
    (net (code "4") (name "/-3V") (class "Default")
      (node (ref "C17") (pin "2") (pinfunction "2_2") (pintype "passive"))
      (node (ref "D100") (pin "C") (pinfunction "C_C") (pintype "passive"))
      (node (ref "D124") (pin "A") (pinfunction "A_A") (pintype "passive"))
      (node (ref "D27") (pin "A") (pinfunction "A_A") (pintype "passive"))
      (node (ref "D53") (pin "A") (pinfunction "A_A") (pintype "passive"))
      (node (ref "D58") (pin "A") (pinfunction "A_A") (pintype "passive"))
      (node (ref "D59") (pin "A") (pinfunction "A_A") (pintype "passive"))
      (node (ref "D64") (pin "A") (pinfunction "A_A") (pintype "passive"))
      (node (ref "D73") (pin "A") (pinfunction "A_A") (pintype "passive"))
      (node (ref "D84") (pin "A") (pinfunction "A_A") (pintype "passive"))
      (node (ref "R56") (pin "2") (pinfunction "2_2") (pintype "passive"))
    )
    (net (code "5") (name "/A-D_CONV") (class "Default")
      (node (ref "D120") (pin "A") (pinfunction "A_A") (pintype "passive"))
      (node (ref "D2") (pin "A") (pinfunction "A_A") (pintype "passive"))
      (node (ref "D3") (pin "A") (pinfunction "A_A") (pintype "passive"))
      (node (ref "U$1") (pin "BP2") (pinfunction "1_BP2") (pintype "bidirectional"))
    )
    (net (code "6") (name "/AC0+1") (class "Default")
      (node (ref "D36") (pin "A") (pinfunction "A_A") (pintype "passive"))
      (node (ref "D39") (pin "A") (pinfunction "A_A") (pintype "passive"))
      (node (ref "U$1") (pin "AT2") (pinfunction "1_AT2") (pintype "bidirectional"))
    )
    (net (code "7") (name "/AC0+2") (class "Default")
      (node (ref "D22") (pin "A") (pinfunction "A_A") (pintype "passive"))
      (node (ref "D26") (pin "A") (pinfunction "A_A") (pintype "passive"))
      (node (ref "U$1") (pin "BD2") (pinfunction "1_BD2") (pintype "bidirectional"))
    )
    (net (code "8") (name "/AC0-1") (class "Default")
      (node (ref "D29") (pin "A") (pinfunction "A_A") (pintype "passive"))
      (node (ref "D31") (pin "A") (pinfunction "A_A") (pintype "passive"))
      (node (ref "U$1") (pin "BA2") (pinfunction "1_BA2") (pintype "bidirectional"))
    )
    (net (code "9") (name "/AC0-2") (class "Default")
      (node (ref "D15") (pin "A") (pinfunction "A_A") (pintype "passive"))
      (node (ref "D17") (pin "A") (pinfunction "A_A") (pintype "passive"))
      (node (ref "U$1") (pin "BF2") (pinfunction "1_BF2") (pintype "bidirectional"))
    )
    (net (code "10") (name "/AC1+1") (class "Default")
      (node (ref "D87") (pin "A") (pinfunction "A_A") (pintype "passive"))
      (node (ref "D89") (pin "A") (pinfunction "A_A") (pintype "passive"))
      (node (ref "U$1") (pin "AU2") (pinfunction "1_AU2") (pintype "bidirectional"))
    )
    (net (code "11") (name "/AC1+2") (class "Default")
      (node (ref "D105") (pin "A") (pinfunction "A_A") (pintype "passive"))
      (node (ref "D99") (pin "A") (pinfunction "A_A") (pintype "passive"))
      (node (ref "U$1") (pin "BE2") (pinfunction "1_BE2") (pintype "bidirectional"))
    )
    (net (code "12") (name "/AC1-1") (class "Default")
      (node (ref "D95") (pin "A") (pinfunction "A_A") (pintype "passive"))
      (node (ref "D97") (pin "A") (pinfunction "A_A") (pintype "passive"))
      (node (ref "U$1") (pin "BB2") (pinfunction "1_BB2") (pintype "bidirectional"))
    )
    (net (code "13") (name "/AC1-2") (class "Default")
      (node (ref "D107") (pin "A") (pinfunction "A_A") (pintype "passive"))
      (node (ref "D109") (pin "A") (pinfunction "A_A") (pintype "passive"))
      (node (ref "U$1") (pin "BH2") (pinfunction "1_BH2") (pintype "bidirectional"))
    )
    (net (code "14") (name "/ADD_ENABLE") (class "Default")
      (node (ref "D43") (pin "A") (pinfunction "A_A") (pintype "passive"))
      (node (ref "U$1") (pin "AL2") (pinfunction "1_AL2") (pintype "bidirectional"))
    )
    (net (code "15") (name "/CARRY_IN") (class "Default")
      (node (ref "C11") (pin "2") (pinfunction "2_2") (pintype "passive"))
      (node (ref "D61") (pin "A") (pinfunction "A_A") (pintype "passive"))
      (node (ref "R32") (pin "2") (pinfunction "2_2") (pintype "passive"))
      (node (ref "R66") (pin "2") (pinfunction "2_2") (pintype "passive"))
      (node (ref "U$1") (pin "AH2") (pinfunction "1_AH2") (pintype "bidirectional"))
    )
    (net (code "16") (name "/CARRY_OUT") (class "Default")
      (node (ref "D53") (pin "C") (pinfunction "C_C") (pintype "passive"))
      (node (ref "Q4") (pin "3") (pinfunction "C_3") (pintype "passive"))
      (node (ref "Q5") (pin "3") (pinfunction "C_3") (pintype "passive"))
      (node (ref "R24") (pin "2") (pinfunction "2_2") (pintype "passive"))
      (node (ref "U$1") (pin "AJ2") (pinfunction "1_AJ2") (pintype "bidirectional"))
    )
    (net (code "17") (name "/CARRY_PULSE") (class "Default")
      (node (ref "D37") (pin "A") (pinfunction "A_A") (pintype "passive"))
      (node (ref "D40") (pin "A") (pinfunction "A_A") (pintype "passive"))
      (node (ref "D76") (pin "A") (pinfunction "A_A") (pintype "passive"))
      (node (ref "U$1") (pin "AD2") (pinfunction "1_AD2") (pintype "bidirectional"))
    )
    (net (code "18") (name "/CLEAR") (class "Default")
      (node (ref "D55") (pin "A") (pinfunction "A_A") (pintype "passive"))
      (node (ref "U$1") (pin "AR2") (pinfunction "1_AR2") (pintype "bidirectional"))
    )
    (net (code "19") (name "/COMP") (class "Default")
      (node (ref "D32") (pin "A") (pinfunction "A_A") (pintype "passive"))
      (node (ref "U$1") (pin "AM2") (pinfunction "1_AM2") (pintype "bidirectional"))
    )
    (net (code "20") (name "/COMPARITOR") (class "Default")
      (node (ref "D4") (pin "A") (pinfunction "A_A") (pintype "passive"))
      (node (ref "D7") (pin "A") (pinfunction "A_A") (pintype "passive"))
      (node (ref "U$1") (pin "BV2") (pinfunction "1_BV2") (pintype "bidirectional"))
    )
    (net (code "21") (name "/HALF_ADD") (class "Default")
      (node (ref "D18") (pin "A") (pinfunction "A_A") (pintype "passive"))
      (node (ref "U$1") (pin "AN2") (pinfunction "1_AN2") (pintype "bidirectional"))
    )
    (net (code "22") (name "/INPUT_MIXER") (class "Default")
      (node (ref "D73") (pin "C") (pinfunction "C_C") (pintype "passive"))
      (node (ref "D74") (pin "A") (pinfunction "A_A") (pintype "passive"))
      (node (ref "R42") (pin "1") (pinfunction "1_1") (pintype "passive"))
      (node (ref "U$1") (pin "AE2") (pinfunction "1_AE2") (pintype "bidirectional"))
    )
    (net (code "23") (name "/MB1") (class "Default")
      (node (ref "D1") (pin "A") (pinfunction "A_A") (pintype "passive"))
      (node (ref "D10") (pin "A") (pinfunction "A_A") (pintype "passive"))
      (node (ref "D12") (pin "A") (pinfunction "A_A") (pintype "passive"))
      (node (ref "D19") (pin "A") (pinfunction "A_A") (pintype "passive"))
      (node (ref "D42") (pin "A") (pinfunction "A_A") (pintype "passive"))
      (node (ref "U$1") (pin "AK2") (pinfunction "1_AK2") (pintype "bidirectional"))
    )
    (net (code "24") (name "/MB1-1") (class "Default")
      (node (ref "D121") (pin "A") (pinfunction "A_A") (pintype "passive"))
      (node (ref "D123") (pin "A") (pinfunction "A_A") (pintype "passive"))
      (node (ref "U$1") (pin "BU2") (pinfunction "1_BU2") (pintype "bidirectional"))
    )
    (net (code "25") (name "/MB_2_AC") (class "Default")
      (node (ref "D8") (pin "A") (pinfunction "A_A") (pintype "passive"))
      (node (ref "D9") (pin "A") (pinfunction "A_A") (pintype "passive"))
      (node (ref "U$1") (pin "BR2") (pinfunction "1_BR2") (pintype "bidirectional"))
    )
    (net (code "26") (name "/ONE") (class "Default")
      (node (ref "D84") (pin "C") (pinfunction "C_C") (pintype "passive"))
      (node (ref "Q11") (pin "3") (pinfunction "C_3") (pintype "passive"))
      (node (ref "R48") (pin "2") (pinfunction "2_2") (pintype "passive"))
      (node (ref "U$1") (pin "AP2") (pinfunction "1_AP2") (pintype "bidirectional"))
    )
    (net (code "27") (name "/RAL") (class "Default")
      (node (ref "D35") (pin "A") (pinfunction "A_A") (pintype "passive"))
      (node (ref "D85") (pin "A") (pinfunction "A_A") (pintype "passive"))
      (node (ref "D86") (pin "A") (pinfunction "A_A") (pintype "passive"))
      (node (ref "U$1") (pin "AV2") (pinfunction "1_AV2") (pintype "bidirectional"))
    )
    (net (code "28") (name "/RAR") (class "Default")
      (node (ref "D28") (pin "A") (pinfunction "A_A") (pintype "passive"))
      (node (ref "D93") (pin "A") (pinfunction "A_A") (pintype "passive"))
      (node (ref "D94") (pin "A") (pinfunction "A_A") (pintype "passive"))
      (node (ref "U$1") (pin "BJ2") (pinfunction "1_BJ2") (pintype "bidirectional"))
    )
    (net (code "29") (name "/RTL") (class "Default")
      (node (ref "D20") (pin "A") (pinfunction "A_A") (pintype "passive"))
      (node (ref "D21") (pin "A") (pinfunction "A_A") (pintype "passive"))
      (node (ref "D98") (pin "A") (pinfunction "A_A") (pintype "passive"))
      (node (ref "U$1") (pin "BK2") (pinfunction "1_BK2") (pintype "bidirectional"))
    )
    (net (code "30") (name "/RTR") (class "Default")
      (node (ref "D106") (pin "A") (pinfunction "A_A") (pintype "passive"))
      (node (ref "D13") (pin "A") (pinfunction "A_A") (pintype "passive"))
      (node (ref "D14") (pin "A") (pinfunction "A_A") (pintype "passive"))
      (node (ref "U$1") (pin "BL2") (pinfunction "1_BL2") (pintype "bidirectional"))
    )
    (net (code "31") (name "/SET") (class "Default")
      (node (ref "D71") (pin "A") (pinfunction "A_A") (pintype "passive"))
      (node (ref "U$1") (pin "AS2") (pinfunction "1_AS2") (pintype "bidirectional"))
    )
    (net (code "32") (name "/SR") (class "Default")
      (node (ref "C21") (pin "1") (pinfunction "1_1") (pintype "passive"))
      (node (ref "D112") (pin "A") (pinfunction "A_A") (pintype "passive"))
      (node (ref "D114") (pin "A") (pinfunction "A_A") (pintype "passive"))
      (node (ref "U$1") (pin "BS2") (pinfunction "1_BS2") (pintype "bidirectional"))
    )
    (net (code "33") (name "/SR_2_AC") (class "Default")
      (node (ref "D110") (pin "A") (pinfunction "A_A") (pintype "passive"))
      (node (ref "D111") (pin "A") (pinfunction "A_A") (pintype "passive"))
      (node (ref "U$1") (pin "BN2") (pinfunction "1_BN2") (pintype "bidirectional"))
    )
    (net (code "34") (name "/TTI") (class "Default")
      (node (ref "D117") (pin "A") (pinfunction "A_A") (pintype "passive"))
      (node (ref "D119") (pin "A") (pinfunction "A_A") (pintype "passive"))
      (node (ref "U$1") (pin "BT2") (pinfunction "1_BT2") (pintype "bidirectional"))
    )
    (net (code "35") (name "/TTI_2_AC") (class "Default")
      (node (ref "D115") (pin "A") (pinfunction "A_A") (pintype "passive"))
      (node (ref "D116") (pin "A") (pinfunction "A_A") (pintype "passive"))
      (node (ref "U$1") (pin "BM2") (pinfunction "1_BM2") (pintype "bidirectional"))
    )
    (net (code "36") (name "/ZERO") (class "Default")
      (node (ref "D124") (pin "C") (pinfunction "C_C") (pintype "passive"))
      (node (ref "Q12") (pin "3") (pinfunction "C_3") (pintype "passive"))
      (node (ref "R54") (pin "2") (pinfunction "2_2") (pintype "passive"))
      (node (ref "U$1") (pin "AF2") (pinfunction "1_AF2") (pintype "bidirectional"))
    )
    (net (code "37") (name "GND") (class "Default")
      (node (ref "C17") (pin "1") (pinfunction "1_1") (pintype "passive"))
      (node (ref "C21") (pin "2") (pinfunction "2_2") (pintype "passive"))
      (node (ref "D103") (pin "A") (pinfunction "A_A") (pintype "passive"))
      (node (ref "D51") (pin "A") (pinfunction "A_A") (pintype "passive"))
      (node (ref "D82") (pin "A") (pinfunction "A_A") (pintype "passive"))
      (node (ref "Q1") (pin "1") (pinfunction "E_1") (pintype "passive"))
      (node (ref "Q10") (pin "1") (pinfunction "E_1") (pintype "passive"))
      (node (ref "Q11") (pin "1") (pinfunction "E_1") (pintype "passive"))
      (node (ref "Q12") (pin "1") (pinfunction "E_1") (pintype "passive"))
      (node (ref "Q2") (pin "1") (pinfunction "E_1") (pintype "passive"))
      (node (ref "Q4") (pin "1") (pinfunction "E_1") (pintype "passive"))
      (node (ref "Q6") (pin "1") (pinfunction "E_1") (pintype "passive"))
      (node (ref "Q7") (pin "1") (pinfunction "E_1") (pintype "passive"))
      (node (ref "Q8") (pin "1") (pinfunction "E_1") (pintype "passive"))
      (node (ref "U$1") (pin "AC2") (pinfunction "1_AC2") (pintype "bidirectional"))
      (node (ref "U$1") (pin "BC2") (pinfunction "1_BC2") (pintype "bidirectional"))
    )
    (net (code "38") (name "Net-(C1-Pad1)") (class "Default")
      (node (ref "C1") (pin "1") (pinfunction "1_1") (pintype "passive"))
      (node (ref "D1") (pin "C") (pinfunction "C_C") (pintype "passive"))
      (node (ref "D2") (pin "C") (pinfunction "C_C") (pintype "passive"))
      (node (ref "D5") (pin "A") (pinfunction "A_A") (pintype "passive"))
      (node (ref "R1") (pin "2") (pinfunction "2_2") (pintype "passive"))
    )
    (net (code "39") (name "Net-(C1-Pad2)") (class "Default")
      (node (ref "C1") (pin "2") (pinfunction "2_2") (pintype "passive"))
      (node (ref "D5") (pin "C") (pinfunction "C_C") (pintype "passive"))
      (node (ref "D6") (pin "A") (pinfunction "A_A") (pintype "passive"))
      (node (ref "D7") (pin "C") (pinfunction "C_C") (pintype "passive"))
      (node (ref "R2") (pin "2") (pinfunction "2_2") (pintype "passive"))
    )
    (net (code "40") (name "Net-(C2-Pad1)") (class "Default")
      (node (ref "C2") (pin "1") (pinfunction "1_1") (pintype "passive"))
      (node (ref "D8") (pin "C") (pinfunction "C_C") (pintype "passive"))
      (node (ref "R3") (pin "2") (pinfunction "2_2") (pintype "passive"))
    )
    (net (code "41") (name "Net-(C2-Pad2)") (class "Default")
      (node (ref "C2") (pin "2") (pinfunction "2_2") (pintype "passive"))
      (node (ref "D11") (pin "A") (pinfunction "A_A") (pintype "passive"))
      (node (ref "D12") (pin "C") (pinfunction "C_C") (pintype "passive"))
      (node (ref "R4") (pin "2") (pinfunction "2_2") (pintype "passive"))
    )
    (net (code "42") (name "Net-(C3-Pad1)") (class "Default")
      (node (ref "C3") (pin "1") (pinfunction "1_1") (pintype "passive"))
      (node (ref "D13") (pin "C") (pinfunction "C_C") (pintype "passive"))
      (node (ref "R5") (pin "2") (pinfunction "2_2") (pintype "passive"))
    )
    (net (code "43") (name "Net-(C3-Pad2)") (class "Default")
      (node (ref "C3") (pin "2") (pinfunction "2_2") (pintype "passive"))
      (node (ref "D16") (pin "A") (pinfunction "A_A") (pintype "passive"))
      (node (ref "D17") (pin "C") (pinfunction "C_C") (pintype "passive"))
      (node (ref "R6") (pin "2") (pinfunction "2_2") (pintype "passive"))
    )
    (net (code "44") (name "Net-(C4-Pad1)") (class "Default")
      (node (ref "C4") (pin "1") (pinfunction "1_1") (pintype "passive"))
      (node (ref "D20") (pin "C") (pinfunction "C_C") (pintype "passive"))
      (node (ref "R7") (pin "2") (pinfunction "2_2") (pintype "passive"))
    )
    (net (code "45") (name "Net-(C4-Pad2)") (class "Default")
      (node (ref "C4") (pin "2") (pinfunction "2_2") (pintype "passive"))
      (node (ref "D25") (pin "A") (pinfunction "A_A") (pintype "passive"))
      (node (ref "D26") (pin "C") (pinfunction "C_C") (pintype "passive"))
      (node (ref "R10") (pin "2") (pinfunction "2_2") (pintype "passive"))
    )
    (net (code "46") (name "Net-(C5-Pad1)") (class "Default")
      (node (ref "C5") (pin "1") (pinfunction "1_1") (pintype "passive"))
      (node (ref "D28") (pin "C") (pinfunction "C_C") (pintype "passive"))
      (node (ref "R12") (pin "2") (pinfunction "2_2") (pintype "passive"))
    )
    (net (code "47") (name "Net-(C5-Pad2)") (class "Default")
      (node (ref "C5") (pin "2") (pinfunction "2_2") (pintype "passive"))
      (node (ref "D30") (pin "A") (pinfunction "A_A") (pintype "passive"))
      (node (ref "D31") (pin "C") (pinfunction "C_C") (pintype "passive"))
      (node (ref "R13") (pin "2") (pinfunction "2_2") (pintype "passive"))
    )
    (net (code "48") (name "Net-(C6-Pad1)") (class "Default")
      (node (ref "C6") (pin "1") (pinfunction "1_1") (pintype "passive"))
      (node (ref "D35") (pin "C") (pinfunction "C_C") (pintype "passive"))
      (node (ref "R14") (pin "2") (pinfunction "2_2") (pintype "passive"))
    )
    (net (code "49") (name "Net-(C6-Pad2)") (class "Default")
      (node (ref "C6") (pin "2") (pinfunction "2_2") (pintype "passive"))
      (node (ref "D38") (pin "A") (pinfunction "A_A") (pintype "passive"))
      (node (ref "D39") (pin "C") (pinfunction "C_C") (pintype "passive"))
      (node (ref "R17") (pin "2") (pinfunction "2_2") (pintype "passive"))
    )
    (net (code "50") (name "Net-(C7-Pad1)") (class "Default")
      (node (ref "C7") (pin "1") (pinfunction "1_1") (pintype "passive"))
      (node (ref "D44") (pin "C") (pinfunction "C_C") (pintype "passive"))
      (node (ref "D45") (pin "C") (pinfunction "C_C") (pintype "passive"))
      (node (ref "R18") (pin "2") (pinfunction "2_2") (pintype "passive"))
    )
    (net (code "51") (name "Net-(C7-Pad2)") (class "Default")
      (node (ref "C7") (pin "2") (pinfunction "2_2") (pintype "passive"))
      (node (ref "D50") (pin "A") (pinfunction "A_A") (pintype "passive"))
      (node (ref "D51") (pin "C") (pinfunction "C_C") (pintype "passive"))
      (node (ref "R22") (pin "2") (pinfunction "2_2") (pintype "passive"))
    )
    (net (code "52") (name "Net-(C8-Pad1)") (class "Default")
      (node (ref "C8") (pin "1") (pinfunction "1_1") (pintype "passive"))
      (node (ref "D40") (pin "C") (pinfunction "C_C") (pintype "passive"))
      (node (ref "D41") (pin "C") (pinfunction "C_C") (pintype "passive"))
      (node (ref "D48") (pin "A") (pinfunction "A_A") (pintype "passive"))
      (node (ref "R19") (pin "2") (pinfunction "2_2") (pintype "passive"))
    )
    (net (code "53") (name "Net-(C12-Pad2)") (class "Default")
      (node (ref "C12") (pin "2") (pinfunction "2_2") (pintype "passive"))
      (node (ref "D70") (pin "A") (pinfunction "A_A") (pintype "passive"))
      (node (ref "D76") (pin "C") (pinfunction "C_C") (pintype "passive"))
      (node (ref "D77") (pin "C") (pinfunction "C_C") (pintype "passive"))
      (node (ref "R40") (pin "2") (pinfunction "2_2") (pintype "passive"))
    )
    (net (code "54") (name "Net-(C14-Pad1)") (class "Default")
      (node (ref "C14") (pin "1") (pinfunction "1_1") (pintype "passive"))
      (node (ref "D72") (pin "C") (pinfunction "C_C") (pintype "passive"))
      (node (ref "D78") (pin "C") (pinfunction "C_C") (pintype "passive"))
      (node (ref "R43") (pin "2") (pinfunction "2_2") (pintype "passive"))
    )
    (net (code "55") (name "Net-(C14-Pad2)") (class "Default")
      (node (ref "C14") (pin "2") (pinfunction "2_2") (pintype "passive"))
      (node (ref "D82") (pin "C") (pinfunction "C_C") (pintype "passive"))
      (node (ref "D83") (pin "A") (pinfunction "A_A") (pintype "passive"))
      (node (ref "R44") (pin "2") (pinfunction "2_2") (pintype "passive"))
    )
    (net (code "56") (name "Net-(C15-Pad1)") (class "Default")
      (node (ref "C15") (pin "1") (pinfunction "1_1") (pintype "passive"))
      (node (ref "D85") (pin "C") (pinfunction "C_C") (pintype "passive"))
      (node (ref "R47") (pin "2") (pinfunction "2_2") (pintype "passive"))
    )
    (net (code "57") (name "Net-(C15-Pad2)") (class "Default")
      (node (ref "C15") (pin "2") (pinfunction "2_2") (pintype "passive"))
      (node (ref "D88") (pin "A") (pinfunction "A_A") (pintype "passive"))
      (node (ref "D89") (pin "C") (pinfunction "C_C") (pintype "passive"))
      (node (ref "R49") (pin "2") (pinfunction "2_2") (pintype "passive"))
    )
    (net (code "58") (name "Net-(C16-Pad1)") (class "Default")
      (node (ref "C16") (pin "1") (pinfunction "1_1") (pintype "passive"))
      (node (ref "D93") (pin "C") (pinfunction "C_C") (pintype "passive"))
      (node (ref "R52") (pin "2") (pinfunction "2_2") (pintype "passive"))
    )
    (net (code "59") (name "Net-(C16-Pad2)") (class "Default")
      (node (ref "C16") (pin "2") (pinfunction "2_2") (pintype "passive"))
      (node (ref "D96") (pin "A") (pinfunction "A_A") (pintype "passive"))
      (node (ref "D97") (pin "C") (pinfunction "C_C") (pintype "passive"))
      (node (ref "R53") (pin "2") (pinfunction "2_2") (pintype "passive"))
    )
    (net (code "60") (name "Net-(C18-Pad1)") (class "Default")
      (node (ref "C18") (pin "1") (pinfunction "1_1") (pintype "passive"))
      (node (ref "D98") (pin "C") (pinfunction "C_C") (pintype "passive"))
      (node (ref "R55") (pin "2") (pinfunction "2_2") (pintype "passive"))
    )
    (net (code "61") (name "Net-(C18-Pad2)") (class "Default")
      (node (ref "C18") (pin "2") (pinfunction "2_2") (pintype "passive"))
      (node (ref "D104") (pin "A") (pinfunction "A_A") (pintype "passive"))
      (node (ref "D105") (pin "C") (pinfunction "C_C") (pintype "passive"))
      (node (ref "R57") (pin "2") (pinfunction "2_2") (pintype "passive"))
    )
    (net (code "62") (name "Net-(C19-Pad1)") (class "Default")
      (node (ref "C19") (pin "1") (pinfunction "1_1") (pintype "passive"))
      (node (ref "D106") (pin "C") (pinfunction "C_C") (pintype "passive"))
      (node (ref "R58") (pin "2") (pinfunction "2_2") (pintype "passive"))
    )
    (net (code "63") (name "Net-(C19-Pad2)") (class "Default")
      (node (ref "C19") (pin "2") (pinfunction "2_2") (pintype "passive"))
      (node (ref "D108") (pin "A") (pinfunction "A_A") (pintype "passive"))
      (node (ref "D109") (pin "C") (pinfunction "C_C") (pintype "passive"))
      (node (ref "R59") (pin "2") (pinfunction "2_2") (pintype "passive"))
    )
    (net (code "64") (name "Net-(C20-Pad1)") (class "Default")
      (node (ref "C20") (pin "1") (pinfunction "1_1") (pintype "passive"))
      (node (ref "D111") (pin "C") (pinfunction "C_C") (pintype "passive"))
      (node (ref "R60") (pin "2") (pinfunction "2_2") (pintype "passive"))
    )
    (net (code "65") (name "Net-(C20-Pad2)") (class "Default")
      (node (ref "C20") (pin "2") (pinfunction "2_2") (pintype "passive"))
      (node (ref "D113") (pin "A") (pinfunction "A_A") (pintype "passive"))
      (node (ref "D114") (pin "C") (pinfunction "C_C") (pintype "passive"))
      (node (ref "R61") (pin "2") (pinfunction "2_2") (pintype "passive"))
    )
    (net (code "66") (name "Net-(C22-Pad1)") (class "Default")
      (node (ref "C22") (pin "1") (pinfunction "1_1") (pintype "passive"))
      (node (ref "D116") (pin "C") (pinfunction "C_C") (pintype "passive"))
      (node (ref "R62") (pin "2") (pinfunction "2_2") (pintype "passive"))
    )
    (net (code "67") (name "Net-(C22-Pad2)") (class "Default")
      (node (ref "C22") (pin "2") (pinfunction "2_2") (pintype "passive"))
      (node (ref "D118") (pin "A") (pinfunction "A_A") (pintype "passive"))
      (node (ref "D119") (pin "C") (pinfunction "C_C") (pintype "passive"))
      (node (ref "R63") (pin "2") (pinfunction "2_2") (pintype "passive"))
    )
    (net (code "68") (name "Net-(C23-Pad1)") (class "Default")
      (node (ref "C23") (pin "1") (pinfunction "1_1") (pintype "passive"))
      (node (ref "D120") (pin "C") (pinfunction "C_C") (pintype "passive"))
      (node (ref "R64") (pin "2") (pinfunction "2_2") (pintype "passive"))
    )
    (net (code "69") (name "Net-(C23-Pad2)") (class "Default")
      (node (ref "C23") (pin "2") (pinfunction "2_2") (pintype "passive"))
      (node (ref "D122") (pin "A") (pinfunction "A_A") (pintype "passive"))
      (node (ref "D123") (pin "C") (pinfunction "C_C") (pintype "passive"))
      (node (ref "R65") (pin "2") (pinfunction "2_2") (pintype "passive"))
    )
    (net (code "70") (name "Net-(D11-PadC)") (class "Default")
      (node (ref "D11") (pin "C") (pinfunction "C_C") (pintype "passive"))
      (node (ref "D16") (pin "C") (pinfunction "C_C") (pintype "passive"))
      (node (ref "D25") (pin "C") (pinfunction "C_C") (pintype "passive"))
      (node (ref "D30") (pin "C") (pinfunction "C_C") (pintype "passive"))
      (node (ref "D38") (pin "C") (pinfunction "C_C") (pintype "passive"))
      (node (ref "D50") (pin "C") (pinfunction "C_C") (pintype "passive"))
      (node (ref "D6") (pin "C") (pinfunction "C_C") (pintype "passive"))
      (node (ref "R67") (pin "1") (pinfunction "1_1") (pintype "passive"))
    )
    (net (code "71") (name "Net-(D18-PadC)") (class "Default")
      (node (ref "D18") (pin "C") (pinfunction "C_C") (pintype "passive"))
      (node (ref "D19") (pin "C") (pinfunction "C_C") (pintype "passive"))
      (node (ref "D23") (pin "C") (pinfunction "C_C") (pintype "passive"))
      (node (ref "R8") (pin "2") (pinfunction "2_2") (pintype "passive"))
    )
    (net (code "72") (name "Net-(D23-PadA)") (class "Default")
      (node (ref "D23") (pin "A") (pinfunction "A_A") (pintype "passive"))
      (node (ref "D24") (pin "C") (pinfunction "C_C") (pintype "passive"))
    )
    (net (code "73") (name "Net-(D32-PadC)") (class "Default")
      (node (ref "D32") (pin "C") (pinfunction "C_C") (pintype "passive"))
      (node (ref "D33") (pin "C") (pinfunction "C_C") (pintype "passive"))
      (node (ref "R15") (pin "2") (pinfunction "2_2") (pintype "passive"))
    )
    (net (code "74") (name "Net-(D33-PadA)") (class "Default")
      (node (ref "D33") (pin "A") (pinfunction "A_A") (pintype "passive"))
      (node (ref "D34") (pin "C") (pinfunction "C_C") (pintype "passive"))
    )
    (net (code "75") (name "Net-(D42-PadC)") (class "Default")
      (node (ref "D42") (pin "C") (pinfunction "C_C") (pintype "passive"))
      (node (ref "D43") (pin "C") (pinfunction "C_C") (pintype "passive"))
      (node (ref "D46") (pin "C") (pinfunction "C_C") (pintype "passive"))
      (node (ref "D49") (pin "C") (pinfunction "C_C") (pintype "passive"))
      (node (ref "R20") (pin "2") (pinfunction "2_2") (pintype "passive"))
    )
    (net (code "76") (name "Net-(D46-PadA)") (class "Default")
      (node (ref "D46") (pin "A") (pinfunction "A_A") (pintype "passive"))
      (node (ref "D47") (pin "C") (pinfunction "C_C") (pintype "passive"))
    )
    (net (code "77") (name "Net-(D54-PadA)") (class "Default")
      (node (ref "D54") (pin "A") (pinfunction "A_A") (pintype "passive"))
      (node (ref "D62") (pin "A") (pinfunction "A_A") (pintype "passive"))
      (node (ref "R66") (pin "1") (pinfunction "1_1") (pintype "passive"))
    )
    (net (code "78") (name "Net-(D55-PadC)") (class "Default")
      (node (ref "D55") (pin "C") (pinfunction "C_C") (pintype "passive"))
      (node (ref "D56") (pin "C") (pinfunction "C_C") (pintype "passive"))
      (node (ref "D60") (pin "C") (pinfunction "C_C") (pintype "passive"))
      (node (ref "R28") (pin "2") (pinfunction "2_2") (pintype "passive"))
    )
    (net (code "79") (name "Net-(D56-PadA)") (class "Default")
      (node (ref "D56") (pin "A") (pinfunction "A_A") (pintype "passive"))
      (node (ref "D57") (pin "C") (pinfunction "C_C") (pintype "passive"))
    )
    (net (code "80") (name "Net-(D63-PadC)") (class "Default")
      (node (ref "D63") (pin "C") (pinfunction "C_C") (pintype "passive"))
      (node (ref "D66") (pin "C") (pinfunction "C_C") (pintype "passive"))
      (node (ref "R38") (pin "2") (pinfunction "2_2") (pintype "passive"))
    )
    (net (code "81") (name "Net-(D65-PadC)") (class "Default")
      (node (ref "D65") (pin "C") (pinfunction "C_C") (pintype "passive"))
      (node (ref "D68") (pin "C") (pinfunction "C_C") (pintype "passive"))
      (node (ref "D71") (pin "C") (pinfunction "C_C") (pintype "passive"))
      (node (ref "D74") (pin "C") (pinfunction "C_C") (pintype "passive"))
      (node (ref "R35") (pin "2") (pinfunction "2_2") (pintype "passive"))
    )
    (net (code "82") (name "Net-(D66-PadA)") (class "Default")
      (node (ref "D66") (pin "A") (pinfunction "A_A") (pintype "passive"))
      (node (ref "D67") (pin "C") (pinfunction "C_C") (pintype "passive"))
    )
    (net (code "83") (name "Net-(D68-PadA)") (class "Default")
      (node (ref "D68") (pin "A") (pinfunction "A_A") (pintype "passive"))
      (node (ref "D69") (pin "C") (pinfunction "C_C") (pintype "passive"))
    )
    (net (code "84") (name "Net-(D79-PadC)") (class "Default")
      (node (ref "D79") (pin "C") (pinfunction "C_C") (pintype "passive"))
      (node (ref "D80") (pin "C") (pinfunction "C_C") (pintype "passive"))
      (node (ref "R45") (pin "2") (pinfunction "2_2") (pintype "passive"))
    )
    (net (code "85") (name "Net-(D80-PadA)") (class "Default")
      (node (ref "D80") (pin "A") (pinfunction "A_A") (pintype "passive"))
      (node (ref "D81") (pin "C") (pinfunction "C_C") (pintype "passive"))
    )
    (net (code "86") (name "Net-(D90-PadC)") (class "Default")
      (node (ref "D90") (pin "C") (pinfunction "C_C") (pintype "passive"))
      (node (ref "D91") (pin "C") (pinfunction "C_C") (pintype "passive"))
      (node (ref "R50") (pin "2") (pinfunction "2_2") (pintype "passive"))
    )
    (net (code "87") (name "Net-(D91-PadA)") (class "Default")
      (node (ref "D91") (pin "A") (pinfunction "A_A") (pintype "passive"))
      (node (ref "D92") (pin "C") (pinfunction "C_C") (pintype "passive"))
    )
    (net (code "88") (name "Net-(D100-PadA)") (class "Default")
      (node (ref "D100") (pin "A") (pinfunction "A_A") (pintype "passive"))
      (node (ref "D101") (pin "C") (pinfunction "C_C") (pintype "passive"))
    )
    (net (code "89") (name "Net-(D101-PadA)") (class "Default")
      (node (ref "D101") (pin "A") (pinfunction "A_A") (pintype "passive"))
      (node (ref "D102") (pin "C") (pinfunction "C_C") (pintype "passive"))
    )
    (net (code "90") (name "Net-(D104-PadC)") (class "Default")
      (node (ref "D104") (pin "C") (pinfunction "C_C") (pintype "passive"))
      (node (ref "D108") (pin "C") (pinfunction "C_C") (pintype "passive"))
      (node (ref "D113") (pin "C") (pinfunction "C_C") (pintype "passive"))
      (node (ref "D118") (pin "C") (pinfunction "C_C") (pintype "passive"))
      (node (ref "D122") (pin "C") (pinfunction "C_C") (pintype "passive"))
      (node (ref "D83") (pin "C") (pinfunction "C_C") (pintype "passive"))
      (node (ref "D88") (pin "C") (pinfunction "C_C") (pintype "passive"))
      (node (ref "D96") (pin "C") (pinfunction "C_C") (pintype "passive"))
      (node (ref "R68") (pin "2") (pinfunction "2_2") (pintype "passive"))
    )
    (net (code "91") (name "Net-(Q1-B)") (class "Default")
      (node (ref "D24") (pin "A") (pinfunction "A_A") (pintype "passive"))
      (node (ref "Q1") (pin "2") (pinfunction "B_2") (pintype "passive"))
      (node (ref "R9") (pin "1") (pinfunction "1_1") (pintype "passive"))
    )
    (net (code "92") (name "Net-(Q1-C)") (class "Default")
      (node (ref "D27") (pin "C") (pinfunction "C_C") (pintype "passive"))
      (node (ref "D44") (pin "A") (pinfunction "A_A") (pintype "passive"))
      (node (ref "D78") (pin "A") (pinfunction "A_A") (pintype "passive"))
      (node (ref "Q1") (pin "3") (pinfunction "C_3") (pintype "passive"))
      (node (ref "Q2") (pin "3") (pinfunction "C_3") (pintype "passive"))
      (node (ref "R11") (pin "2") (pinfunction "2_2") (pintype "passive"))
    )
    (net (code "93") (name "Net-(Q2-B)") (class "Default")
      (node (ref "D34") (pin "A") (pinfunction "A_A") (pintype "passive"))
      (node (ref "Q2") (pin "2") (pinfunction "B_2") (pintype "passive"))
      (node (ref "R16") (pin "1") (pinfunction "1_1") (pintype "passive"))
    )
    (net (code "94") (name "Net-(Q3-B)") (class "Default")
      (node (ref "C8") (pin "2") (pinfunction "2_2") (pintype "passive"))
      (node (ref "D48") (pin "C") (pinfunction "C_C") (pintype "passive"))
      (node (ref "D54") (pin "C") (pinfunction "C_C") (pintype "passive"))
      (node (ref "Q3") (pin "2") (pinfunction "B_2") (pintype "passive"))
      (node (ref "R23") (pin "2") (pinfunction "2_2") (pintype "passive"))
    )
    (net (code "95") (name "Net-(Q3-C)") (class "Default")
      (node (ref "Q3") (pin "3") (pinfunction "C_3") (pintype "passive"))
      (node (ref "R26") (pin "1") (pinfunction "1_1") (pintype "passive"))
    )
    (net (code "96") (name "Net-(Q3-E)") (class "Default")
      (node (ref "C10") (pin "1") (pinfunction "1_1") (pintype "passive"))
      (node (ref "D57") (pin "A") (pinfunction "A_A") (pintype "passive"))
      (node (ref "Q3") (pin "1") (pinfunction "E_1") (pintype "passive"))
      (node (ref "Q7") (pin "2") (pinfunction "B_2") (pintype "passive"))
      (node (ref "R29") (pin "1") (pinfunction "1_1") (pintype "passive"))
      (node (ref "R67") (pin "2") (pinfunction "2_2") (pintype "passive"))
    )
    (net (code "97") (name "Net-(Q4-B)") (class "Default")
      (node (ref "D47") (pin "A") (pinfunction "A_A") (pintype "passive"))
      (node (ref "Q4") (pin "2") (pinfunction "B_2") (pintype "passive"))
      (node (ref "R21") (pin "1") (pinfunction "1_1") (pintype "passive"))
    )
    (net (code "98") (name "Net-(Q5-B)") (class "Default")
      (node (ref "C9") (pin "1") (pinfunction "1_1") (pintype "passive"))
      (node (ref "Q5") (pin "2") (pinfunction "B_2") (pintype "passive"))
      (node (ref "R27") (pin "1") (pinfunction "1_1") (pintype "passive"))
    )
    (net (code "99") (name "Net-(Q6-B)") (class "Default")
      (node (ref "C11") (pin "1") (pinfunction "1_1") (pintype "passive"))
      (node (ref "Q6") (pin "2") (pinfunction "B_2") (pintype "passive"))
      (node (ref "R32") (pin "1") (pinfunction "1_1") (pintype "passive"))
    )
    (net (code "100") (name "Net-(Q6-C)") (class "Default")
      (node (ref "C9") (pin "2") (pinfunction "2_2") (pintype "passive"))
      (node (ref "D58") (pin "C") (pinfunction "C_C") (pintype "passive"))
      (node (ref "Q6") (pin "3") (pinfunction "C_3") (pintype "passive"))
      (node (ref "R27") (pin "2") (pinfunction "2_2") (pintype "passive"))
      (node (ref "R30") (pin "2") (pinfunction "2_2") (pintype "passive"))
    )
    (net (code "101") (name "Net-(Q7-C)") (class "Default")
      (node (ref "C13") (pin "2") (pinfunction "2_2") (pintype "passive"))
      (node (ref "D49") (pin "A") (pinfunction "A_A") (pintype "passive"))
      (node (ref "D64") (pin "C") (pinfunction "C_C") (pintype "passive"))
      (node (ref "D65") (pin "A") (pinfunction "A_A") (pintype "passive"))
      (node (ref "D72") (pin "A") (pinfunction "A_A") (pintype "passive"))
      (node (ref "D77") (pin "A") (pinfunction "A_A") (pintype "passive"))
      (node (ref "D79") (pin "A") (pinfunction "A_A") (pintype "passive"))
      (node (ref "Q7") (pin "3") (pinfunction "C_3") (pintype "passive"))
      (node (ref "R34") (pin "2") (pinfunction "2_2") (pintype "passive"))
    )
    (net (code "102") (name "Net-(Q8-B)") (class "Default")
      (node (ref "C13") (pin "1") (pinfunction "1_1") (pintype "passive"))
      (node (ref "D69") (pin "A") (pinfunction "A_A") (pintype "passive"))
      (node (ref "Q8") (pin "2") (pinfunction "B_2") (pintype "passive"))
      (node (ref "Q9") (pin "1") (pinfunction "E_1") (pintype "passive"))
      (node (ref "R36") (pin "1") (pinfunction "1_1") (pintype "passive"))
      (node (ref "R68") (pin "1") (pinfunction "1_1") (pintype "passive"))
    )
    (net (code "103") (name "Net-(Q8-C)") (class "Default")
      (node (ref "C10") (pin "2") (pinfunction "2_2") (pintype "passive"))
      (node (ref "D41") (pin "A") (pinfunction "A_A") (pintype "passive"))
      (node (ref "D45") (pin "A") (pinfunction "A_A") (pintype "passive"))
      (node (ref "D59") (pin "C") (pinfunction "C_C") (pintype "passive"))
      (node (ref "D60") (pin "A") (pinfunction "A_A") (pintype "passive"))
      (node (ref "D63") (pin "A") (pinfunction "A_A") (pintype "passive"))
      (node (ref "D90") (pin "A") (pinfunction "A_A") (pintype "passive"))
      (node (ref "Q8") (pin "3") (pinfunction "C_3") (pintype "passive"))
      (node (ref "R31") (pin "2") (pinfunction "2_2") (pintype "passive"))
    )
    (net (code "104") (name "Net-(Q9-B)") (class "Default")
      (node (ref "C12") (pin "1") (pinfunction "1_1") (pintype "passive"))
      (node (ref "D62") (pin "C") (pinfunction "C_C") (pintype "passive"))
      (node (ref "D70") (pin "C") (pinfunction "C_C") (pintype "passive"))
      (node (ref "Q9") (pin "2") (pinfunction "B_2") (pintype "passive"))
      (node (ref "R37") (pin "2") (pinfunction "2_2") (pintype "passive"))
    )
    (net (code "105") (name "Net-(Q9-C)") (class "Default")
      (node (ref "Q9") (pin "3") (pinfunction "C_3") (pintype "passive"))
      (node (ref "R33") (pin "2") (pinfunction "2_2") (pintype "passive"))
    )
    (net (code "106") (name "Net-(Q10-B)") (class "Default")
      (node (ref "D67") (pin "A") (pinfunction "A_A") (pintype "passive"))
      (node (ref "Q10") (pin "2") (pinfunction "B_2") (pintype "passive"))
      (node (ref "R39") (pin "1") (pinfunction "1_1") (pintype "passive"))
    )
    (net (code "107") (name "Net-(Q10-C)") (class "Default")
      (node (ref "Q10") (pin "3") (pinfunction "C_3") (pintype "passive"))
      (node (ref "Q5") (pin "1") (pinfunction "E_1") (pintype "passive"))
    )
    (net (code "108") (name "Net-(Q11-B)") (class "Default")
      (node (ref "D81") (pin "A") (pinfunction "A_A") (pintype "passive"))
      (node (ref "Q11") (pin "2") (pinfunction "B_2") (pintype "passive"))
      (node (ref "R46") (pin "1") (pinfunction "1_1") (pintype "passive"))
    )
    (net (code "109") (name "Net-(Q12-B)") (class "Default")
      (node (ref "D92") (pin "A") (pinfunction "A_A") (pintype "passive"))
      (node (ref "Q12") (pin "2") (pinfunction "B_2") (pintype "passive"))
      (node (ref "R51") (pin "1") (pinfunction "1_1") (pintype "passive"))
    )
  )
)
